# 03_DO.net
KiCad netlist of a schematic drawn in Altium Designer
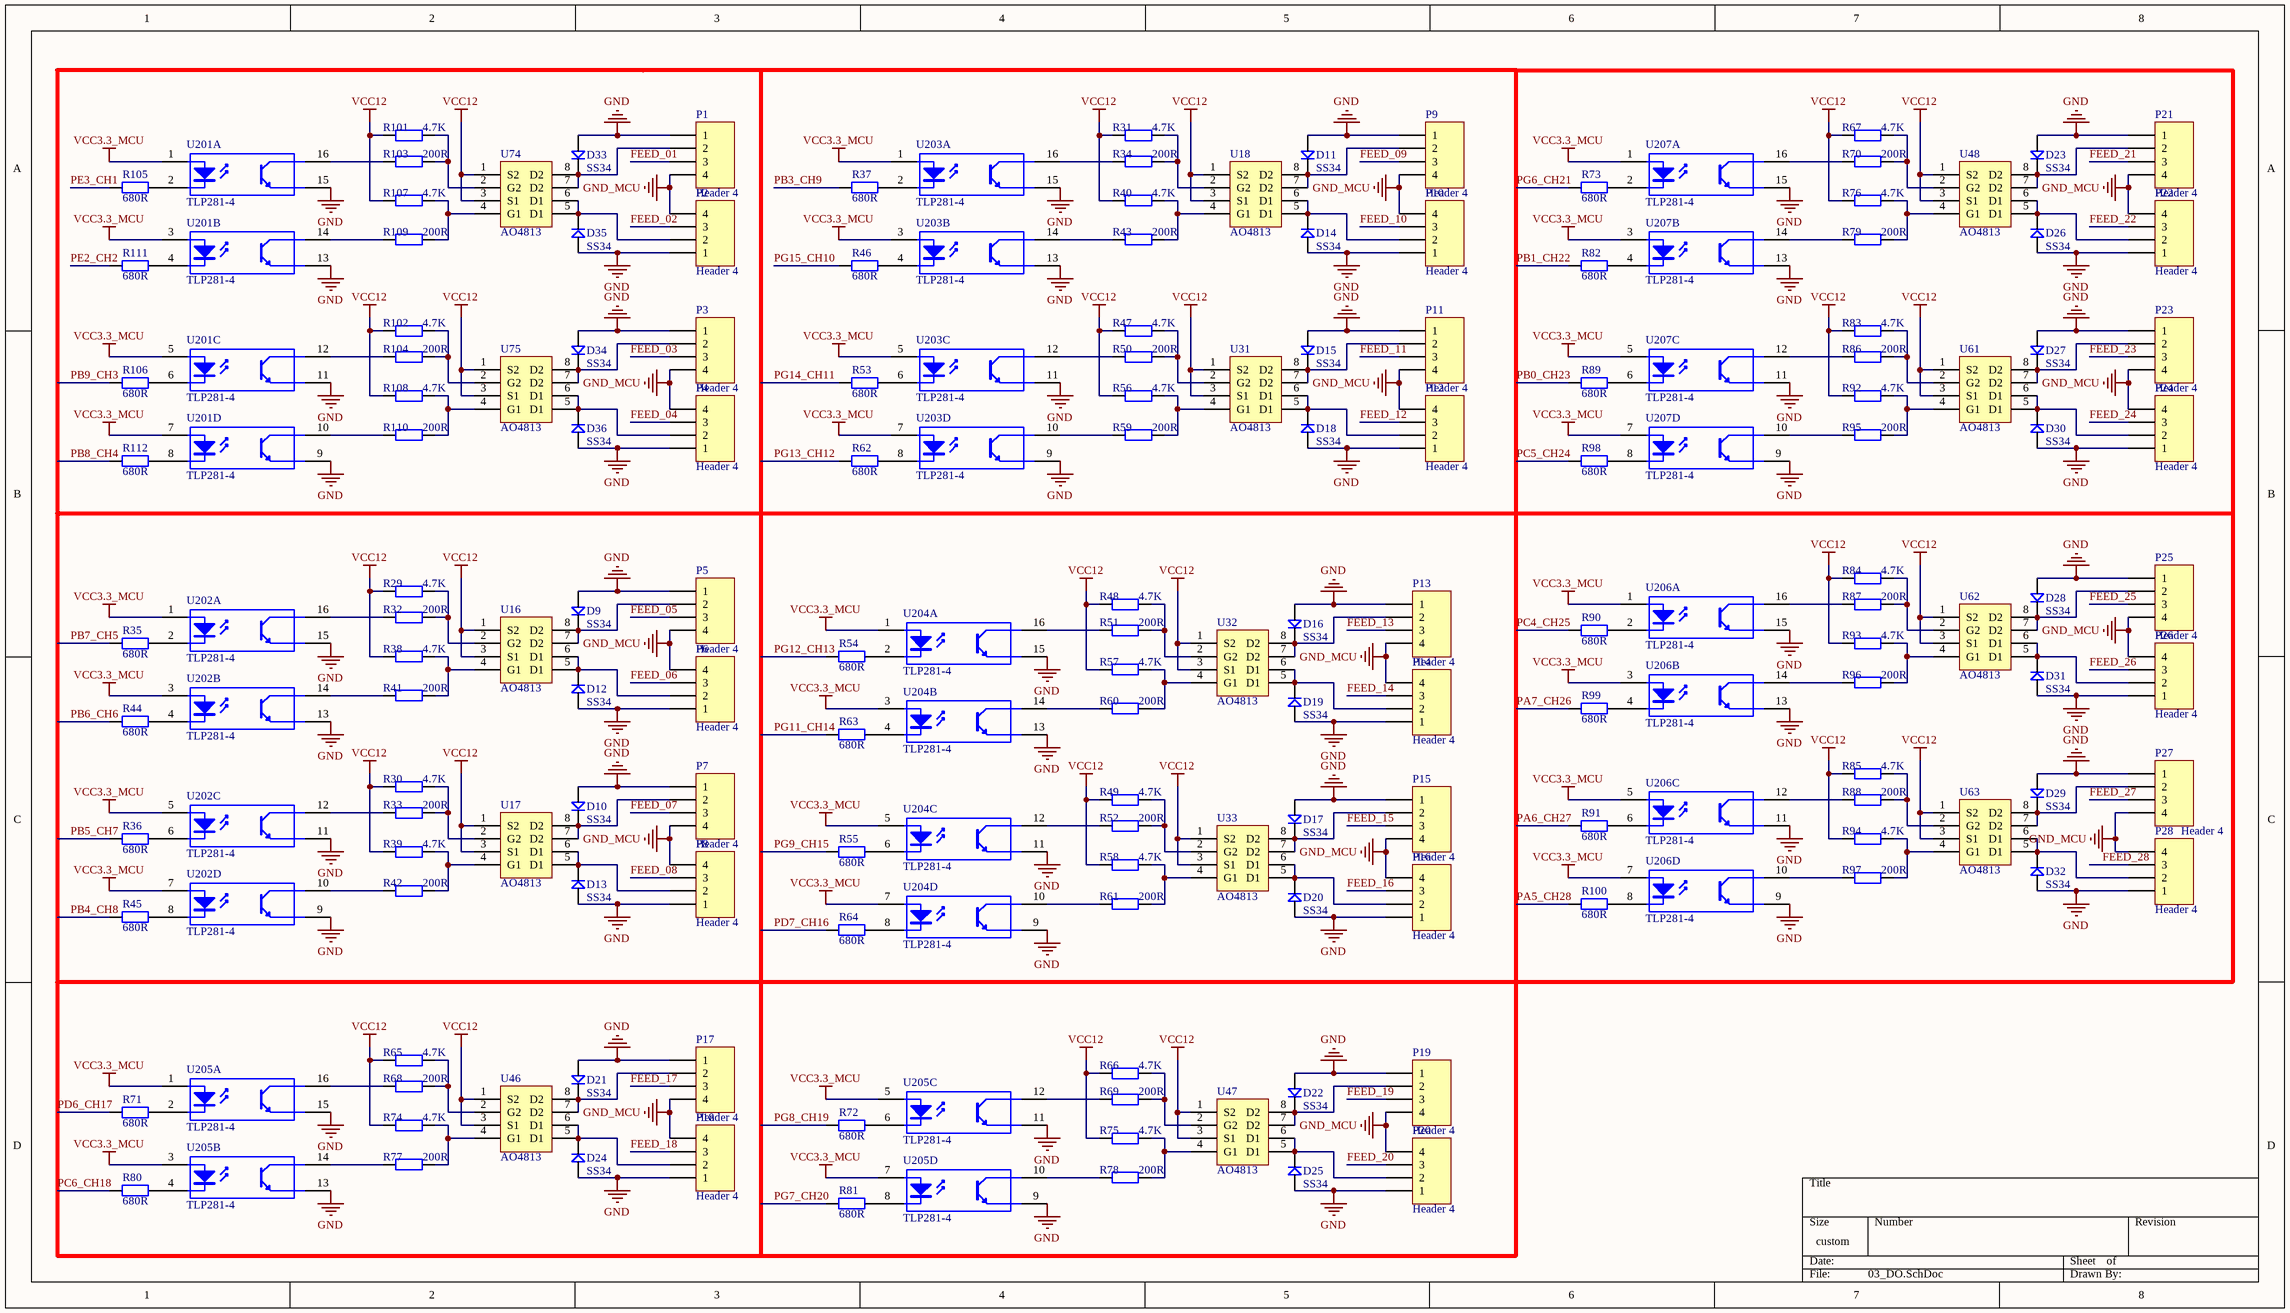
[diagram p0: 03_DO.SchDoc]

(export (version "E")
  (design (tool "Eeschema 10.0.6"))
  (components
    (comp (ref "D9") (value "SS34") (footprint "D1812") (libsource (lib "Explorer STM32F407封装库") (part "D")))
    (comp (ref "D10") (value "SS34") (footprint "D1812") (libsource (lib "Explorer STM32F407封装库") (part "D")))
    (comp (ref "D11") (value "SS34") (footprint "D1812") (libsource (lib "Explorer STM32F407封装库") (part "D")))
    (comp (ref "D12") (value "SS34") (footprint "D1812") (libsource (lib "Explorer STM32F407封装库") (part "D")))
    (comp (ref "D13") (value "SS34") (footprint "D1812") (libsource (lib "Explorer STM32F407封装库") (part "D")))
    (comp (ref "D14") (value "SS34") (footprint "D1812") (libsource (lib "Explorer STM32F407封装库") (part "D")))
    (comp (ref "D15") (value "SS34") (footprint "D1812") (libsource (lib "Explorer STM32F407封装库") (part "D")))
    (comp (ref "D16") (value "SS34") (footprint "D1812") (libsource (lib "Explorer STM32F407封装库") (part "D")))
    (comp (ref "D17") (value "SS34") (footprint "D1812") (libsource (lib "Explorer STM32F407封装库") (part "D")))
    (comp (ref "D18") (value "SS34") (footprint "D1812") (libsource (lib "Explorer STM32F407封装库") (part "D")))
    (comp (ref "D19") (value "SS34") (footprint "D1812") (libsource (lib "Explorer STM32F407封装库") (part "D")))
    (comp (ref "D20") (value "SS34") (footprint "D1812") (libsource (lib "Explorer STM32F407封装库") (part "D")))
    (comp (ref "D21") (value "SS34") (footprint "D1812") (libsource (lib "Explorer STM32F407封装库") (part "D")))
    (comp (ref "D22") (value "SS34") (footprint "D1812") (libsource (lib "Explorer STM32F407封装库") (part "D")))
    (comp (ref "D23") (value "SS34") (footprint "D1812") (libsource (lib "Explorer STM32F407封装库") (part "D")))
    (comp (ref "D24") (value "SS34") (footprint "D1812") (libsource (lib "Explorer STM32F407封装库") (part "D")))
    (comp (ref "D25") (value "SS34") (footprint "D1812") (libsource (lib "Explorer STM32F407封装库") (part "D")))
    (comp (ref "D26") (value "SS34") (footprint "D1812") (libsource (lib "Explorer STM32F407封装库") (part "D")))
    (comp (ref "D27") (value "SS34") (footprint "D1812") (libsource (lib "Explorer STM32F407封装库") (part "D")))
    (comp (ref "D28") (value "SS34") (footprint "D1812") (libsource (lib "Explorer STM32F407封装库") (part "D")))
    (comp (ref "D29") (value "SS34") (footprint "D1812") (libsource (lib "Explorer STM32F407封装库") (part "D")))
    (comp (ref "D30") (value "SS34") (footprint "D1812") (libsource (lib "Explorer STM32F407封装库") (part "D")))
    (comp (ref "D31") (value "SS34") (footprint "D1812") (libsource (lib "Explorer STM32F407封装库") (part "D")))
    (comp (ref "D32") (value "SS34") (footprint "D1812") (libsource (lib "Explorer STM32F407封装库") (part "D")))
    (comp (ref "D33") (value "SS34") (footprint "D1812") (libsource (lib "Explorer STM32F407封装库") (part "D")))
    (comp (ref "D34") (value "SS34") (footprint "D1812") (libsource (lib "Explorer STM32F407封装库") (part "D")))
    (comp (ref "D35") (value "SS34") (footprint "D1812") (libsource (lib "Explorer STM32F407封装库") (part "D")))
    (comp (ref "D36") (value "SS34") (footprint "D1812") (libsource (lib "Explorer STM32F407封装库") (part "D")))
    (comp (ref "P1")
      (value "Header 4")
      (footprint "XH2.54-1*10")
      (description "Header, 4-Pin")
      (fields (field (name "PUBLISHER") "Altium Limited"))
      (libsource (lib "Miscellaneous Connectors") (part "Header 4"))
    )
    (comp (ref "P2")
      (value "Header 4")
      (footprint "XH2.54-1*10")
      (description "Header, 4-Pin")
      (fields (field (name "PUBLISHER") "Altium Limited"))
      (libsource (lib "") (part "Header 4_1"))
    )
    (comp (ref "P3")
      (value "Header 4")
      (footprint "XH2.54-1*10")
      (description "Header, 4-Pin")
      (fields (field (name "PUBLISHER") "Altium Limited"))
      (libsource (lib "Miscellaneous Connectors") (part "Header 4"))
    )
    (comp (ref "P4")
      (value "Header 4")
      (footprint "XH2.54-1*10")
      (description "Header, 4-Pin")
      (fields (field (name "PUBLISHER") "Altium Limited"))
      (libsource (lib "") (part "Header 4_1"))
    )
    (comp (ref "P5")
      (value "Header 4")
      (footprint "XH2.54-1*10")
      (description "Header, 4-Pin")
      (fields (field (name "PUBLISHER") "Altium Limited"))
      (libsource (lib "Miscellaneous Connectors") (part "Header 4"))
    )
    (comp (ref "P6")
      (value "Header 4")
      (footprint "XH2.54-1*10")
      (description "Header, 4-Pin")
      (fields (field (name "PUBLISHER") "Altium Limited"))
      (libsource (lib "") (part "Header 4_1"))
    )
    (comp (ref "P7")
      (value "Header 4")
      (footprint "XH2.54-1*10")
      (description "Header, 4-Pin")
      (fields (field (name "PUBLISHER") "Altium Limited"))
      (libsource (lib "Miscellaneous Connectors") (part "Header 4"))
    )
    (comp (ref "P8")
      (value "Header 4")
      (footprint "XH2.54-1*10")
      (description "Header, 4-Pin")
      (fields (field (name "PUBLISHER") "Altium Limited"))
      (libsource (lib "") (part "Header 4_1"))
    )
    (comp (ref "P9")
      (value "Header 4")
      (footprint "XH2.54-1*10")
      (description "Header, 4-Pin")
      (fields (field (name "PUBLISHER") "Altium Limited"))
      (libsource (lib "Miscellaneous Connectors") (part "Header 4"))
    )
    (comp (ref "P10")
      (value "Header 4")
      (footprint "XH2.54-1*10")
      (description "Header, 4-Pin")
      (fields (field (name "PUBLISHER") "Altium Limited"))
      (libsource (lib "") (part "Header 4_1"))
    )
    (comp (ref "P11")
      (value "Header 4")
      (footprint "XH2.54-1*10")
      (description "Header, 4-Pin")
      (fields (field (name "PUBLISHER") "Altium Limited"))
      (libsource (lib "Miscellaneous Connectors") (part "Header 4"))
    )
    (comp (ref "P12")
      (value "Header 4")
      (footprint "XH2.54-1*10")
      (description "Header, 4-Pin")
      (fields (field (name "PUBLISHER") "Altium Limited"))
      (libsource (lib "") (part "Header 4_1"))
    )
    (comp (ref "P13")
      (value "Header 4")
      (footprint "XH2.54-1*10")
      (description "Header, 4-Pin")
      (fields (field (name "PUBLISHER") "Altium Limited"))
      (libsource (lib "Miscellaneous Connectors") (part "Header 4"))
    )
    (comp (ref "P14")
      (value "Header 4")
      (footprint "XH2.54-1*10")
      (description "Header, 4-Pin")
      (fields (field (name "PUBLISHER") "Altium Limited"))
      (libsource (lib "") (part "Header 4_1"))
    )
    (comp (ref "P15")
      (value "Header 4")
      (footprint "XH2.54-1*10")
      (description "Header, 4-Pin")
      (fields (field (name "PUBLISHER") "Altium Limited"))
      (libsource (lib "Miscellaneous Connectors") (part "Header 4"))
    )
    (comp (ref "P16")
      (value "Header 4")
      (footprint "XH2.54-1*10")
      (description "Header, 4-Pin")
      (fields (field (name "PUBLISHER") "Altium Limited"))
      (libsource (lib "") (part "Header 4_1"))
    )
    (comp (ref "P17")
      (value "Header 4")
      (footprint "XH2.54-1*10")
      (description "Header, 4-Pin")
      (fields (field (name "PUBLISHER") "Altium Limited"))
      (libsource (lib "Miscellaneous Connectors") (part "Header 4"))
    )
    (comp (ref "P18")
      (value "Header 4")
      (footprint "XH2.54-1*10")
      (description "Header, 4-Pin")
      (fields (field (name "PUBLISHER") "Altium Limited"))
      (libsource (lib "") (part "Header 4_1"))
    )
    (comp (ref "P19")
      (value "Header 4")
      (footprint "XH2.54-1*10")
      (description "Header, 4-Pin")
      (fields (field (name "PUBLISHER") "Altium Limited"))
      (libsource (lib "Miscellaneous Connectors") (part "Header 4"))
    )
    (comp (ref "P20")
      (value "Header 4")
      (footprint "XH2.54-1*10")
      (description "Header, 4-Pin")
      (fields (field (name "PUBLISHER") "Altium Limited"))
      (libsource (lib "") (part "Header 4_1"))
    )
    (comp (ref "P21")
      (value "Header 4")
      (footprint "XH2.54-1*10")
      (description "Header, 4-Pin")
      (fields (field (name "PUBLISHER") "Altium Limited"))
      (libsource (lib "Miscellaneous Connectors") (part "Header 4"))
    )
    (comp (ref "P22")
      (value "Header 4")
      (footprint "XH2.54-1*10")
      (description "Header, 4-Pin")
      (fields (field (name "PUBLISHER") "Altium Limited"))
      (libsource (lib "") (part "Header 4_1"))
    )
    (comp (ref "P23")
      (value "Header 4")
      (footprint "XH2.54-1*10")
      (description "Header, 4-Pin")
      (fields (field (name "PUBLISHER") "Altium Limited"))
      (libsource (lib "Miscellaneous Connectors") (part "Header 4"))
    )
    (comp (ref "P24")
      (value "Header 4")
      (footprint "XH2.54-1*10")
      (description "Header, 4-Pin")
      (fields (field (name "PUBLISHER") "Altium Limited"))
      (libsource (lib "") (part "Header 4_1"))
    )
    (comp (ref "P25")
      (value "Header 4")
      (footprint "XH2.54-1*10")
      (description "Header, 4-Pin")
      (fields (field (name "PUBLISHER") "Altium Limited"))
      (libsource (lib "Miscellaneous Connectors") (part "Header 4"))
    )
    (comp (ref "P26")
      (value "Header 4")
      (footprint "XH2.54-1*10")
      (description "Header, 4-Pin")
      (fields (field (name "PUBLISHER") "Altium Limited"))
      (libsource (lib "") (part "Header 4_1"))
    )
    (comp (ref "P27")
      (value "Header 4")
      (footprint "XH2.54-1*10")
      (description "Header, 4-Pin")
      (fields (field (name "PUBLISHER") "Altium Limited"))
      (libsource (lib "Miscellaneous Connectors") (part "Header 4"))
    )
    (comp (ref "P28")
      (value "Header 4")
      (footprint "XH2.54-1*10")
      (description "Header, 4-Pin")
      (fields (field (name "PUBLISHER") "Altium Limited"))
      (libsource (lib "") (part "Header 4_1"))
    )
    (comp (ref "R29")
      (value "4.7K")
      (footprint "0603R")
      (description "贴片电阻")
      (libsource (lib "Miscellaneous Devices LC") (part "0603 2.7KΩ (2701) 1%"))
    )
    (comp (ref "R30")
      (value "4.7K")
      (footprint "0603R")
      (description "贴片电阻")
      (libsource (lib "Miscellaneous Devices LC") (part "0603 2.7KΩ (2701) 1%"))
    )
    (comp (ref "R31")
      (value "4.7K")
      (footprint "0603R")
      (description "贴片电阻")
      (libsource (lib "Miscellaneous Devices LC") (part "0603 2.7KΩ (2701) 1%"))
    )
    (comp (ref "R32")
      (value "200R")
      (footprint "0603R")
      (description "贴片电阻")
      (libsource (lib "CD's_LIB_2018") (part "0603 2.7KΩ (2701) 1%"))
    )
    (comp (ref "R33")
      (value "200R")
      (footprint "0603R")
      (description "贴片电阻")
      (libsource (lib "CD's_LIB_2018") (part "0603 2.7KΩ (2701) 1%"))
    )
    (comp (ref "R34")
      (value "200R")
      (footprint "0603R")
      (description "贴片电阻")
      (libsource (lib "CD's_LIB_2018") (part "0603 2.7KΩ (2701) 1%"))
    )
    (comp (ref "R35")
      (value "680R")
      (footprint "0603R")
      (description "贴片电阻")
      (libsource (lib "CD's_LIB_2018") (part "0603 2.7KΩ (2701) 1%"))
    )
    (comp (ref "R36")
      (value "680R")
      (footprint "0603R")
      (description "贴片电阻")
      (libsource (lib "CD's_LIB_2018") (part "0603 2.7KΩ (2701) 1%"))
    )
    (comp (ref "R37")
      (value "680R")
      (footprint "0603R")
      (description "贴片电阻")
      (libsource (lib "CD's_LIB_2018") (part "0603 2.7KΩ (2701) 1%"))
    )
    (comp (ref "R38")
      (value "4.7K")
      (footprint "0603R")
      (description "贴片电阻")
      (libsource (lib "Miscellaneous Devices LC") (part "0603 2.7KΩ (2701) 1%"))
    )
    (comp (ref "R39")
      (value "4.7K")
      (footprint "0603R")
      (description "贴片电阻")
      (libsource (lib "Miscellaneous Devices LC") (part "0603 2.7KΩ (2701) 1%"))
    )
    (comp (ref "R40")
      (value "4.7K")
      (footprint "0603R")
      (description "贴片电阻")
      (libsource (lib "Miscellaneous Devices LC") (part "0603 2.7KΩ (2701) 1%"))
    )
    (comp (ref "R41")
      (value "200R")
      (footprint "0603R")
      (description "贴片电阻")
      (libsource (lib "CD's_LIB_2018") (part "0603 2.7KΩ (2701) 1%"))
    )
    (comp (ref "R42")
      (value "200R")
      (footprint "0603R")
      (description "贴片电阻")
      (libsource (lib "CD's_LIB_2018") (part "0603 2.7KΩ (2701) 1%"))
    )
    (comp (ref "R43")
      (value "200R")
      (footprint "0603R")
      (description "贴片电阻")
      (libsource (lib "CD's_LIB_2018") (part "0603 2.7KΩ (2701) 1%"))
    )
    (comp (ref "R44")
      (value "680R")
      (footprint "0603R")
      (description "贴片电阻")
      (libsource (lib "CD's_LIB_2018") (part "0603 2.7KΩ (2701) 1%"))
    )
    (comp (ref "R45")
      (value "680R")
      (footprint "0603R")
      (description "贴片电阻")
      (libsource (lib "CD's_LIB_2018") (part "0603 2.7KΩ (2701) 1%"))
    )
    (comp (ref "R46")
      (value "680R")
      (footprint "0603R")
      (description "贴片电阻")
      (libsource (lib "CD's_LIB_2018") (part "0603 2.7KΩ (2701) 1%"))
    )
    (comp (ref "R47")
      (value "4.7K")
      (footprint "0603R")
      (description "贴片电阻")
      (libsource (lib "Miscellaneous Devices LC") (part "0603 2.7KΩ (2701) 1%"))
    )
    (comp (ref "R48")
      (value "4.7K")
      (footprint "0603R")
      (description "贴片电阻")
      (libsource (lib "Miscellaneous Devices LC") (part "0603 2.7KΩ (2701) 1%"))
    )
    (comp (ref "R49")
      (value "4.7K")
      (footprint "0603R")
      (description "贴片电阻")
      (libsource (lib "Miscellaneous Devices LC") (part "0603 2.7KΩ (2701) 1%"))
    )
    (comp (ref "R50")
      (value "200R")
      (footprint "0603R")
      (description "贴片电阻")
      (libsource (lib "CD's_LIB_2018") (part "0603 2.7KΩ (2701) 1%"))
    )
    (comp (ref "R51")
      (value "200R")
      (footprint "0603R")
      (description "贴片电阻")
      (libsource (lib "CD's_LIB_2018") (part "0603 2.7KΩ (2701) 1%"))
    )
    (comp (ref "R52")
      (value "200R")
      (footprint "0603R")
      (description "贴片电阻")
      (libsource (lib "CD's_LIB_2018") (part "0603 2.7KΩ (2701) 1%"))
    )
    (comp (ref "R53")
      (value "680R")
      (footprint "0603R")
      (description "贴片电阻")
      (libsource (lib "CD's_LIB_2018") (part "0603 2.7KΩ (2701) 1%"))
    )
    (comp (ref "R54")
      (value "680R")
      (footprint "0603R")
      (description "贴片电阻")
      (libsource (lib "CD's_LIB_2018") (part "0603 2.7KΩ (2701) 1%"))
    )
    (comp (ref "R55")
      (value "680R")
      (footprint "0603R")
      (description "贴片电阻")
      (libsource (lib "CD's_LIB_2018") (part "0603 2.7KΩ (2701) 1%"))
    )
    (comp (ref "R56")
      (value "4.7K")
      (footprint "0603R")
      (description "贴片电阻")
      (libsource (lib "Miscellaneous Devices LC") (part "0603 2.7KΩ (2701) 1%"))
    )
    (comp (ref "R57")
      (value "4.7K")
      (footprint "0603R")
      (description "贴片电阻")
      (libsource (lib "Miscellaneous Devices LC") (part "0603 2.7KΩ (2701) 1%"))
    )
    (comp (ref "R58")
      (value "4.7K")
      (footprint "0603R")
      (description "贴片电阻")
      (libsource (lib "Miscellaneous Devices LC") (part "0603 2.7KΩ (2701) 1%"))
    )
    (comp (ref "R59")
      (value "200R")
      (footprint "0603R")
      (description "贴片电阻")
      (libsource (lib "CD's_LIB_2018") (part "0603 2.7KΩ (2701) 1%"))
    )
    (comp (ref "R60")
      (value "200R")
      (footprint "0603R")
      (description "贴片电阻")
      (libsource (lib "CD's_LIB_2018") (part "0603 2.7KΩ (2701) 1%"))
    )
    (comp (ref "R61")
      (value "200R")
      (footprint "0603R")
      (description "贴片电阻")
      (libsource (lib "CD's_LIB_2018") (part "0603 2.7KΩ (2701) 1%"))
    )
    (comp (ref "R62")
      (value "680R")
      (footprint "0603R")
      (description "贴片电阻")
      (libsource (lib "CD's_LIB_2018") (part "0603 2.7KΩ (2701) 1%"))
    )
    (comp (ref "R63")
      (value "680R")
      (footprint "0603R")
      (description "贴片电阻")
      (libsource (lib "CD's_LIB_2018") (part "0603 2.7KΩ (2701) 1%"))
    )
    (comp (ref "R64")
      (value "680R")
      (footprint "0603R")
      (description "贴片电阻")
      (libsource (lib "CD's_LIB_2018") (part "0603 2.7KΩ (2701) 1%"))
    )
    (comp (ref "R65")
      (value "4.7K")
      (footprint "0603R")
      (description "贴片电阻")
      (libsource (lib "Miscellaneous Devices LC") (part "0603 2.7KΩ (2701) 1%"))
    )
    (comp (ref "R66")
      (value "4.7K")
      (footprint "0603R")
      (description "贴片电阻")
      (libsource (lib "Miscellaneous Devices LC") (part "0603 2.7KΩ (2701) 1%"))
    )
    (comp (ref "R67")
      (value "4.7K")
      (footprint "0603R")
      (description "贴片电阻")
      (libsource (lib "Miscellaneous Devices LC") (part "0603 2.7KΩ (2701) 1%"))
    )
    (comp (ref "R68")
      (value "200R")
      (footprint "0603R")
      (description "贴片电阻")
      (libsource (lib "CD's_LIB_2018") (part "0603 2.7KΩ (2701) 1%"))
    )
    (comp (ref "R69")
      (value "200R")
      (footprint "0603R")
      (description "贴片电阻")
      (libsource (lib "CD's_LIB_2018") (part "0603 2.7KΩ (2701) 1%"))
    )
    (comp (ref "R70")
      (value "200R")
      (footprint "0603R")
      (description "贴片电阻")
      (libsource (lib "CD's_LIB_2018") (part "0603 2.7KΩ (2701) 1%"))
    )
    (comp (ref "R71")
      (value "680R")
      (footprint "0603R")
      (description "贴片电阻")
      (libsource (lib "CD's_LIB_2018") (part "0603 2.7KΩ (2701) 1%"))
    )
    (comp (ref "R72")
      (value "680R")
      (footprint "0603R")
      (description "贴片电阻")
      (libsource (lib "CD's_LIB_2018") (part "0603 2.7KΩ (2701) 1%"))
    )
    (comp (ref "R73")
      (value "680R")
      (footprint "0603R")
      (description "贴片电阻")
      (libsource (lib "CD's_LIB_2018") (part "0603 2.7KΩ (2701) 1%"))
    )
    (comp (ref "R74")
      (value "4.7K")
      (footprint "0603R")
      (description "贴片电阻")
      (libsource (lib "Miscellaneous Devices LC") (part "0603 2.7KΩ (2701) 1%"))
    )
    (comp (ref "R75")
      (value "4.7K")
      (footprint "0603R")
      (description "贴片电阻")
      (libsource (lib "Miscellaneous Devices LC") (part "0603 2.7KΩ (2701) 1%"))
    )
    (comp (ref "R76")
      (value "4.7K")
      (footprint "0603R")
      (description "贴片电阻")
      (libsource (lib "Miscellaneous Devices LC") (part "0603 2.7KΩ (2701) 1%"))
    )
    (comp (ref "R77")
      (value "200R")
      (footprint "0603R")
      (description "贴片电阻")
      (libsource (lib "CD's_LIB_2018") (part "0603 2.7KΩ (2701) 1%"))
    )
    (comp (ref "R78")
      (value "200R")
      (footprint "0603R")
      (description "贴片电阻")
      (libsource (lib "CD's_LIB_2018") (part "0603 2.7KΩ (2701) 1%"))
    )
    (comp (ref "R79")
      (value "200R")
      (footprint "0603R")
      (description "贴片电阻")
      (libsource (lib "CD's_LIB_2018") (part "0603 2.7KΩ (2701) 1%"))
    )
    (comp (ref "R80")
      (value "680R")
      (footprint "0603R")
      (description "贴片电阻")
      (libsource (lib "CD's_LIB_2018") (part "0603 2.7KΩ (2701) 1%"))
    )
    (comp (ref "R81")
      (value "680R")
      (footprint "0603R")
      (description "贴片电阻")
      (libsource (lib "CD's_LIB_2018") (part "0603 2.7KΩ (2701) 1%"))
    )
    (comp (ref "R82")
      (value "680R")
      (footprint "0603R")
      (description "贴片电阻")
      (libsource (lib "CD's_LIB_2018") (part "0603 2.7KΩ (2701) 1%"))
    )
    (comp (ref "R83")
      (value "4.7K")
      (footprint "0603R")
      (description "贴片电阻")
      (libsource (lib "Miscellaneous Devices LC") (part "0603 2.7KΩ (2701) 1%"))
    )
    (comp (ref "R84")
      (value "4.7K")
      (footprint "0603R")
      (description "贴片电阻")
      (libsource (lib "Miscellaneous Devices LC") (part "0603 2.7KΩ (2701) 1%"))
    )
    (comp (ref "R85")
      (value "4.7K")
      (footprint "0603R")
      (description "贴片电阻")
      (libsource (lib "Miscellaneous Devices LC") (part "0603 2.7KΩ (2701) 1%"))
    )
    (comp (ref "R86")
      (value "200R")
      (footprint "0603R")
      (description "贴片电阻")
      (libsource (lib "CD's_LIB_2018") (part "0603 2.7KΩ (2701) 1%"))
    )
    (comp (ref "R87")
      (value "200R")
      (footprint "0603R")
      (description "贴片电阻")
      (libsource (lib "CD's_LIB_2018") (part "0603 2.7KΩ (2701) 1%"))
    )
    (comp (ref "R88")
      (value "200R")
      (footprint "0603R")
      (description "贴片电阻")
      (libsource (lib "CD's_LIB_2018") (part "0603 2.7KΩ (2701) 1%"))
    )
    (comp (ref "R89")
      (value "680R")
      (footprint "0603R")
      (description "贴片电阻")
      (libsource (lib "CD's_LIB_2018") (part "0603 2.7KΩ (2701) 1%"))
    )
    (comp (ref "R90")
      (value "680R")
      (footprint "0603R")
      (description "贴片电阻")
      (libsource (lib "CD's_LIB_2018") (part "0603 2.7KΩ (2701) 1%"))
    )
    (comp (ref "R91")
      (value "680R")
      (footprint "0603R")
      (description "贴片电阻")
      (libsource (lib "CD's_LIB_2018") (part "0603 2.7KΩ (2701) 1%"))
    )
    (comp (ref "R92")
      (value "4.7K")
      (footprint "0603R")
      (description "贴片电阻")
      (libsource (lib "Miscellaneous Devices LC") (part "0603 2.7KΩ (2701) 1%"))
    )
    (comp (ref "R93")
      (value "4.7K")
      (footprint "0603R")
      (description "贴片电阻")
      (libsource (lib "Miscellaneous Devices LC") (part "0603 2.7KΩ (2701) 1%"))
    )
    (comp (ref "R94")
      (value "4.7K")
      (footprint "0603R")
      (description "贴片电阻")
      (libsource (lib "Miscellaneous Devices LC") (part "0603 2.7KΩ (2701) 1%"))
    )
    (comp (ref "R95")
      (value "200R")
      (footprint "0603R")
      (description "贴片电阻")
      (libsource (lib "CD's_LIB_2018") (part "0603 2.7KΩ (2701) 1%"))
    )
    (comp (ref "R96")
      (value "200R")
      (footprint "0603R")
      (description "贴片电阻")
      (libsource (lib "CD's_LIB_2018") (part "0603 2.7KΩ (2701) 1%"))
    )
    (comp (ref "R97")
      (value "200R")
      (footprint "0603R")
      (description "贴片电阻")
      (libsource (lib "CD's_LIB_2018") (part "0603 2.7KΩ (2701) 1%"))
    )
    (comp (ref "R98")
      (value "680R")
      (footprint "0603R")
      (description "贴片电阻")
      (libsource (lib "CD's_LIB_2018") (part "0603 2.7KΩ (2701) 1%"))
    )
    (comp (ref "R99")
      (value "680R")
      (footprint "0603R")
      (description "贴片电阻")
      (libsource (lib "CD's_LIB_2018") (part "0603 2.7KΩ (2701) 1%"))
    )
    (comp (ref "R100")
      (value "680R")
      (footprint "0603R")
      (description "贴片电阻")
      (libsource (lib "CD's_LIB_2018") (part "0603 2.7KΩ (2701) 1%"))
    )
    (comp (ref "R101")
      (value "4.7K")
      (footprint "0603R")
      (description "贴片电阻")
      (libsource (lib "Miscellaneous Devices LC") (part "0603 2.7KΩ (2701) 1%"))
    )
    (comp (ref "R102")
      (value "4.7K")
      (footprint "0603R")
      (description "贴片电阻")
      (libsource (lib "Miscellaneous Devices LC") (part "0603 2.7KΩ (2701) 1%"))
    )
    (comp (ref "R103")
      (value "200R")
      (footprint "0603R")
      (description "贴片电阻")
      (libsource (lib "CD's_LIB_2018") (part "0603 2.7KΩ (2701) 1%"))
    )
    (comp (ref "R104")
      (value "200R")
      (footprint "0603R")
      (description "贴片电阻")
      (libsource (lib "CD's_LIB_2018") (part "0603 2.7KΩ (2701) 1%"))
    )
    (comp (ref "R105")
      (value "680R")
      (footprint "0603R")
      (description "贴片电阻")
      (libsource (lib "CD's_LIB_2018") (part "0603 2.7KΩ (2701) 1%"))
    )
    (comp (ref "R106")
      (value "680R")
      (footprint "0603R")
      (description "贴片电阻")
      (libsource (lib "CD's_LIB_2018") (part "0603 2.7KΩ (2701) 1%"))
    )
    (comp (ref "R107")
      (value "4.7K")
      (footprint "0603R")
      (description "贴片电阻")
      (libsource (lib "Miscellaneous Devices LC") (part "0603 2.7KΩ (2701) 1%"))
    )
    (comp (ref "R108")
      (value "4.7K")
      (footprint "0603R")
      (description "贴片电阻")
      (libsource (lib "Miscellaneous Devices LC") (part "0603 2.7KΩ (2701) 1%"))
    )
    (comp (ref "R109")
      (value "200R")
      (footprint "0603R")
      (description "贴片电阻")
      (libsource (lib "CD's_LIB_2018") (part "0603 2.7KΩ (2701) 1%"))
    )
    (comp (ref "R110")
      (value "200R")
      (footprint "0603R")
      (description "贴片电阻")
      (libsource (lib "CD's_LIB_2018") (part "0603 2.7KΩ (2701) 1%"))
    )
    (comp (ref "R111")
      (value "680R")
      (footprint "0603R")
      (description "贴片电阻")
      (libsource (lib "CD's_LIB_2018") (part "0603 2.7KΩ (2701) 1%"))
    )
    (comp (ref "R112")
      (value "680R")
      (footprint "0603R")
      (description "贴片电阻")
      (libsource (lib "CD's_LIB_2018") (part "0603 2.7KΩ (2701) 1%"))
    )
    (comp (ref "U16") (value "AO4813") (footprint "SO-8") (libsource (lib "NDS8434") (part "NDS8434")))
    (comp (ref "U17") (value "AO4813") (footprint "SO-8") (libsource (lib "NDS8434") (part "NDS8434")))
    (comp (ref "U18") (value "AO4813") (footprint "SO-8") (libsource (lib "NDS8434") (part "NDS8434")))
    (comp (ref "U31") (value "AO4813") (footprint "SO-8") (libsource (lib "NDS8434") (part "NDS8434")))
    (comp (ref "U32") (value "AO4813") (footprint "SO-8") (libsource (lib "NDS8434") (part "NDS8434")))
    (comp (ref "U33") (value "AO4813") (footprint "SO-8") (libsource (lib "NDS8434") (part "NDS8434")))
    (comp (ref "U46") (value "AO4813") (footprint "SO-8") (libsource (lib "NDS8434") (part "NDS8434")))
    (comp (ref "U47") (value "AO4813") (footprint "SO-8") (libsource (lib "NDS8434") (part "NDS8434")))
    (comp (ref "U48") (value "AO4813") (footprint "SO-8") (libsource (lib "NDS8434") (part "NDS8434")))
    (comp (ref "U61") (value "AO4813") (footprint "SO-8") (libsource (lib "NDS8434") (part "NDS8434")))
    (comp (ref "U62") (value "AO4813") (footprint "SO-8") (libsource (lib "NDS8434") (part "NDS8434")))
    (comp (ref "U63") (value "AO4813") (footprint "SO-8") (libsource (lib "NDS8434") (part "NDS8434")))
    (comp (ref "U74") (value "AO4813") (footprint "SO-8") (libsource (lib "NDS8434") (part "NDS8434")))
    (comp (ref "U75") (value "AO4813") (footprint "SO-8") (libsource (lib "NDS8434") (part "NDS8434")))
    (comp (ref "U201")
      (value "TLP281-4")
      (footprint "SO-16")
      (libsource (lib "CD's_LIB_2018") (part "TP521-4_1"))
    )
    (comp (ref "U202")
      (value "TLP281-4")
      (footprint "SO-16")
      (libsource (lib "CD's_LIB_2018") (part "TP521-4_1"))
    )
    (comp (ref "U203")
      (value "TLP281-4")
      (footprint "SO-16")
      (libsource (lib "CD's_LIB_2018") (part "TP521-4_1"))
    )
    (comp (ref "U204")
      (value "TLP281-4")
      (footprint "SO-16")
      (libsource (lib "CD's_LIB_2018") (part "TP521-4_1"))
    )
    (comp (ref "U205")
      (value "TLP281-4")
      (footprint "SO-16")
      (libsource (lib "CD's_LIB_2018") (part "TP521-4_1"))
    )
    (comp (ref "U206")
      (value "TLP281-4")
      (footprint "SO-16")
      (libsource (lib "CD's_LIB_2018") (part "TP521-4_1"))
    )
    (comp (ref "U207")
      (value "TLP281-4")
      (footprint "SO-16")
      (libsource (lib "CD's_LIB_2018") (part "TP521-4_1"))
    )
  )
  (nets
    (net (code "1") (name "/FEED_01") (class "Default")
      (node (ref "P1") (pin "3") (pinfunction "3_3") (pintype "passive"))
    )
    (net (code "2") (name "/FEED_02") (class "Default")
      (node (ref "P2") (pin "3") (pinfunction "3_3") (pintype "passive"))
    )
    (net (code "3") (name "/FEED_03") (class "Default")
      (node (ref "P3") (pin "3") (pinfunction "3_3") (pintype "passive"))
    )
    (net (code "4") (name "/FEED_04") (class "Default")
      (node (ref "P4") (pin "3") (pinfunction "3_3") (pintype "passive"))
    )
    (net (code "5") (name "/FEED_05") (class "Default")
      (node (ref "P5") (pin "3") (pinfunction "3_3") (pintype "passive"))
    )
    (net (code "6") (name "/FEED_06") (class "Default")
      (node (ref "P6") (pin "3") (pinfunction "3_3") (pintype "passive"))
    )
    (net (code "7") (name "/FEED_07") (class "Default")
      (node (ref "P7") (pin "3") (pinfunction "3_3") (pintype "passive"))
    )
    (net (code "8") (name "/FEED_08") (class "Default")
      (node (ref "P8") (pin "3") (pinfunction "3_3") (pintype "passive"))
    )
    (net (code "9") (name "/FEED_09") (class "Default")
      (node (ref "P9") (pin "3") (pinfunction "3_3") (pintype "passive"))
    )
    (net (code "10") (name "/FEED_10") (class "Default")
      (node (ref "P10") (pin "3") (pinfunction "3_3") (pintype "passive"))
    )
    (net (code "11") (name "/FEED_11") (class "Default")
      (node (ref "P11") (pin "3") (pinfunction "3_3") (pintype "passive"))
    )
    (net (code "12") (name "/FEED_12") (class "Default")
      (node (ref "P12") (pin "3") (pinfunction "3_3") (pintype "passive"))
    )
    (net (code "13") (name "/FEED_13") (class "Default")
      (node (ref "P13") (pin "3") (pinfunction "3_3") (pintype "passive"))
    )
    (net (code "14") (name "/FEED_14") (class "Default")
      (node (ref "P14") (pin "3") (pinfunction "3_3") (pintype "passive"))
    )
    (net (code "15") (name "/FEED_15") (class "Default")
      (node (ref "P15") (pin "3") (pinfunction "3_3") (pintype "passive"))
    )
    (net (code "16") (name "/FEED_16") (class "Default")
      (node (ref "P16") (pin "3") (pinfunction "3_3") (pintype "passive"))
    )
    (net (code "17") (name "/FEED_17") (class "Default")
      (node (ref "P17") (pin "3") (pinfunction "3_3") (pintype "passive"))
    )
    (net (code "18") (name "/FEED_18") (class "Default")
      (node (ref "P18") (pin "3") (pinfunction "3_3") (pintype "passive"))
    )
    (net (code "19") (name "/FEED_19") (class "Default")
      (node (ref "P19") (pin "3") (pinfunction "3_3") (pintype "passive"))
    )
    (net (code "20") (name "/FEED_20") (class "Default")
      (node (ref "P20") (pin "3") (pinfunction "3_3") (pintype "passive"))
    )
    (net (code "21") (name "/FEED_21") (class "Default")
      (node (ref "P21") (pin "3") (pinfunction "3_3") (pintype "passive"))
    )
    (net (code "22") (name "/FEED_22") (class "Default")
      (node (ref "P22") (pin "3") (pinfunction "3_3") (pintype "passive"))
    )
    (net (code "23") (name "/FEED_23") (class "Default")
      (node (ref "P23") (pin "3") (pinfunction "3_3") (pintype "passive"))
    )
    (net (code "24") (name "/FEED_24") (class "Default")
      (node (ref "P24") (pin "3") (pinfunction "3_3") (pintype "passive"))
    )
    (net (code "25") (name "/FEED_25") (class "Default")
      (node (ref "P25") (pin "3") (pinfunction "3_3") (pintype "passive"))
    )
    (net (code "26") (name "/FEED_26") (class "Default")
      (node (ref "P26") (pin "3") (pinfunction "3_3") (pintype "passive"))
    )
    (net (code "27") (name "/FEED_27") (class "Default")
      (node (ref "P27") (pin "3") (pinfunction "3_3") (pintype "passive"))
    )
    (net (code "28") (name "/FEED_28") (class "Default")
      (node (ref "P28") (pin "3") (pinfunction "3_3") (pintype "passive"))
    )
    (net (code "29") (name "/PA5_CH28") (class "Default")
      (node (ref "R100") (pin "1") (pinfunction "1_1") (pintype "passive"))
    )
    (net (code "30") (name "/PA6_CH27") (class "Default")
      (node (ref "R91") (pin "1") (pinfunction "1_1") (pintype "passive"))
    )
    (net (code "31") (name "/PA7_CH26") (class "Default")
      (node (ref "R99") (pin "1") (pinfunction "1_1") (pintype "passive"))
    )
    (net (code "32") (name "/PB0_CH23") (class "Default")
      (node (ref "R89") (pin "1") (pinfunction "1_1") (pintype "passive"))
    )
    (net (code "33") (name "/PB1_CH22") (class "Default")
      (node (ref "R82") (pin "1") (pinfunction "1_1") (pintype "passive"))
    )
    (net (code "34") (name "/PB3_CH9") (class "Default")
      (node (ref "R37") (pin "1") (pinfunction "1_1") (pintype "passive"))
    )
    (net (code "35") (name "/PB4_CH8") (class "Default")
      (node (ref "R45") (pin "1") (pinfunction "1_1") (pintype "passive"))
    )
    (net (code "36") (name "/PB5_CH7") (class "Default")
      (node (ref "R36") (pin "1") (pinfunction "1_1") (pintype "passive"))
    )
    (net (code "37") (name "/PB6_CH6") (class "Default")
      (node (ref "R44") (pin "1") (pinfunction "1_1") (pintype "passive"))
    )
    (net (code "38") (name "/PB7_CH5") (class "Default")
      (node (ref "R35") (pin "1") (pinfunction "1_1") (pintype "passive"))
    )
    (net (code "39") (name "/PB8_CH4") (class "Default")
      (node (ref "R112") (pin "1") (pinfunction "1_1") (pintype "passive"))
    )
    (net (code "40") (name "/PB9_CH3") (class "Default")
      (node (ref "R106") (pin "1") (pinfunction "1_1") (pintype "passive"))
    )
    (net (code "41") (name "/PC4_CH25") (class "Default")
      (node (ref "R90") (pin "1") (pinfunction "1_1") (pintype "passive"))
    )
    (net (code "42") (name "/PC5_CH24") (class "Default")
      (node (ref "R98") (pin "1") (pinfunction "1_1") (pintype "passive"))
    )
    (net (code "43") (name "/PC6_CH18") (class "Default")
      (node (ref "R80") (pin "1") (pinfunction "1_1") (pintype "passive"))
    )
    (net (code "44") (name "/PD6_CH17") (class "Default")
      (node (ref "R71") (pin "1") (pinfunction "1_1") (pintype "passive"))
    )
    (net (code "45") (name "/PD7_CH16") (class "Default")
      (node (ref "R64") (pin "1") (pinfunction "1_1") (pintype "passive"))
    )
    (net (code "46") (name "/PE2_CH2") (class "Default")
      (node (ref "R111") (pin "1") (pinfunction "1_1") (pintype "passive"))
    )
    (net (code "47") (name "/PE3_CH1") (class "Default")
      (node (ref "R105") (pin "1") (pinfunction "1_1") (pintype "passive"))
    )
    (net (code "48") (name "/PG6_CH21") (class "Default")
      (node (ref "R73") (pin "1") (pinfunction "1_1") (pintype "passive"))
    )
    (net (code "49") (name "/PG7_CH20") (class "Default")
      (node (ref "R81") (pin "1") (pinfunction "1_1") (pintype "passive"))
    )
    (net (code "50") (name "/PG8_CH19") (class "Default")
      (node (ref "R72") (pin "1") (pinfunction "1_1") (pintype "passive"))
    )
    (net (code "51") (name "/PG9_CH15") (class "Default")
      (node (ref "R55") (pin "1") (pinfunction "1_1") (pintype "passive"))
    )
    (net (code "52") (name "/PG11_CH14") (class "Default")
      (node (ref "R63") (pin "1") (pinfunction "1_1") (pintype "passive"))
    )
    (net (code "53") (name "/PG12_CH13") (class "Default")
      (node (ref "R54") (pin "1") (pinfunction "1_1") (pintype "passive"))
    )
    (net (code "54") (name "/PG13_CH12") (class "Default")
      (node (ref "R62") (pin "1") (pinfunction "1_1") (pintype "passive"))
    )
    (net (code "55") (name "/PG14_CH11") (class "Default")
      (node (ref "R53") (pin "1") (pinfunction "1_1") (pintype "passive"))
    )
    (net (code "56") (name "/PG15_CH10") (class "Default")
      (node (ref "R46") (pin "1") (pinfunction "1_1") (pintype "passive"))
    )
    (net (code "57") (name "GND") (class "Default")
      (node (ref "D10") (pin "1") (pintype "passive"))
      (node (ref "D11") (pin "1") (pintype "passive"))
      (node (ref "D12") (pin "1") (pintype "passive"))
      (node (ref "D13") (pin "1") (pintype "passive"))
      (node (ref "D14") (pin "1") (pintype "passive"))
      (node (ref "D15") (pin "1") (pintype "passive"))
      (node (ref "D16") (pin "1") (pintype "passive"))
      (node (ref "D17") (pin "1") (pintype "passive"))
      (node (ref "D18") (pin "1") (pintype "passive"))
      (node (ref "D19") (pin "1") (pintype "passive"))
      (node (ref "D20") (pin "1") (pintype "passive"))
      (node (ref "D21") (pin "1") (pintype "passive"))
      (node (ref "D22") (pin "1") (pintype "passive"))
      (node (ref "D23") (pin "1") (pintype "passive"))
      (node (ref "D24") (pin "1") (pintype "passive"))
      (node (ref "D25") (pin "1") (pintype "passive"))
      (node (ref "D26") (pin "1") (pintype "passive"))
      (node (ref "D27") (pin "1") (pintype "passive"))
      (node (ref "D28") (pin "1") (pintype "passive"))
      (node (ref "D29") (pin "1") (pintype "passive"))
      (node (ref "D30") (pin "1") (pintype "passive"))
      (node (ref "D31") (pin "1") (pintype "passive"))
      (node (ref "D32") (pin "1") (pintype "passive"))
      (node (ref "D33") (pin "1") (pintype "passive"))
      (node (ref "D34") (pin "1") (pintype "passive"))
      (node (ref "D35") (pin "1") (pintype "passive"))
      (node (ref "D36") (pin "1") (pintype "passive"))
      (node (ref "D9") (pin "1") (pintype "passive"))
      (node (ref "P1") (pin "1") (pinfunction "1_1") (pintype "passive"))
      (node (ref "P10") (pin "1") (pinfunction "1_1") (pintype "passive"))
      (node (ref "P11") (pin "1") (pinfunction "1_1") (pintype "passive"))
      (node (ref "P12") (pin "1") (pinfunction "1_1") (pintype "passive"))
      (node (ref "P13") (pin "1") (pinfunction "1_1") (pintype "passive"))
      (node (ref "P14") (pin "1") (pinfunction "1_1") (pintype "passive"))
      (node (ref "P15") (pin "1") (pinfunction "1_1") (pintype "passive"))
      (node (ref "P16") (pin "1") (pinfunction "1_1") (pintype "passive"))
      (node (ref "P17") (pin "1") (pinfunction "1_1") (pintype "passive"))
      (node (ref "P18") (pin "1") (pinfunction "1_1") (pintype "passive"))
      (node (ref "P19") (pin "1") (pinfunction "1_1") (pintype "passive"))
      (node (ref "P2") (pin "1") (pinfunction "1_1") (pintype "passive"))
      (node (ref "P20") (pin "1") (pinfunction "1_1") (pintype "passive"))
      (node (ref "P21") (pin "1") (pinfunction "1_1") (pintype "passive"))
      (node (ref "P22") (pin "1") (pinfunction "1_1") (pintype "passive"))
      (node (ref "P23") (pin "1") (pinfunction "1_1") (pintype "passive"))
      (node (ref "P24") (pin "1") (pinfunction "1_1") (pintype "passive"))
      (node (ref "P25") (pin "1") (pinfunction "1_1") (pintype "passive"))
      (node (ref "P26") (pin "1") (pinfunction "1_1") (pintype "passive"))
      (node (ref "P27") (pin "1") (pinfunction "1_1") (pintype "passive"))
      (node (ref "P28") (pin "1") (pinfunction "1_1") (pintype "passive"))
      (node (ref "P3") (pin "1") (pinfunction "1_1") (pintype "passive"))
      (node (ref "P4") (pin "1") (pinfunction "1_1") (pintype "passive"))
      (node (ref "P5") (pin "1") (pinfunction "1_1") (pintype "passive"))
      (node (ref "P6") (pin "1") (pinfunction "1_1") (pintype "passive"))
      (node (ref "P7") (pin "1") (pinfunction "1_1") (pintype "passive"))
      (node (ref "P8") (pin "1") (pinfunction "1_1") (pintype "passive"))
      (node (ref "P9") (pin "1") (pinfunction "1_1") (pintype "passive"))
      (node (ref "U201") (pin "11") (pinfunction "E_11") (pintype "passive"))
      (node (ref "U201") (pin "13") (pinfunction "E_13") (pintype "passive"))
      (node (ref "U201") (pin "15") (pinfunction "E_15") (pintype "passive"))
      (node (ref "U201") (pin "9") (pinfunction "E_9") (pintype "passive"))
      (node (ref "U202") (pin "11") (pinfunction "E_11") (pintype "passive"))
      (node (ref "U202") (pin "13") (pinfunction "E_13") (pintype "passive"))
      (node (ref "U202") (pin "15") (pinfunction "E_15") (pintype "passive"))
      (node (ref "U202") (pin "9") (pinfunction "E_9") (pintype "passive"))
      (node (ref "U203") (pin "11") (pinfunction "E_11") (pintype "passive"))
      (node (ref "U203") (pin "13") (pinfunction "E_13") (pintype "passive"))
      (node (ref "U203") (pin "15") (pinfunction "E_15") (pintype "passive"))
      (node (ref "U203") (pin "9") (pinfunction "E_9") (pintype "passive"))
      (node (ref "U204") (pin "11") (pinfunction "E_11") (pintype "passive"))
      (node (ref "U204") (pin "13") (pinfunction "E_13") (pintype "passive"))
      (node (ref "U204") (pin "15") (pinfunction "E_15") (pintype "passive"))
      (node (ref "U204") (pin "9") (pinfunction "E_9") (pintype "passive"))
      (node (ref "U205") (pin "11") (pinfunction "E_11") (pintype "passive"))
      (node (ref "U205") (pin "13") (pinfunction "E_13") (pintype "passive"))
      (node (ref "U205") (pin "15") (pinfunction "E_15") (pintype "passive"))
      (node (ref "U205") (pin "9") (pinfunction "E_9") (pintype "passive"))
      (node (ref "U206") (pin "11") (pinfunction "E_11") (pintype "passive"))
      (node (ref "U206") (pin "13") (pinfunction "E_13") (pintype "passive"))
      (node (ref "U206") (pin "15") (pinfunction "E_15") (pintype "passive"))
      (node (ref "U206") (pin "9") (pinfunction "E_9") (pintype "passive"))
      (node (ref "U207") (pin "11") (pinfunction "E_11") (pintype "passive"))
      (node (ref "U207") (pin "13") (pinfunction "E_13") (pintype "passive"))
      (node (ref "U207") (pin "15") (pinfunction "E_15") (pintype "passive"))
      (node (ref "U207") (pin "9") (pinfunction "E_9") (pintype "passive"))
    )
    (net (code "58") (name "GND_MCU") (class "Default")
      (node (ref "P1") (pin "4") (pinfunction "4_4") (pintype "passive"))
      (node (ref "P10") (pin "4") (pinfunction "4_4") (pintype "passive"))
      (node (ref "P11") (pin "4") (pinfunction "4_4") (pintype "passive"))
      (node (ref "P12") (pin "4") (pinfunction "4_4") (pintype "passive"))
      (node (ref "P13") (pin "4") (pinfunction "4_4") (pintype "passive"))
      (node (ref "P14") (pin "4") (pinfunction "4_4") (pintype "passive"))
      (node (ref "P15") (pin "4") (pinfunction "4_4") (pintype "passive"))
      (node (ref "P16") (pin "4") (pinfunction "4_4") (pintype "passive"))
      (node (ref "P17") (pin "4") (pinfunction "4_4") (pintype "passive"))
      (node (ref "P18") (pin "4") (pinfunction "4_4") (pintype "passive"))
      (node (ref "P19") (pin "4") (pinfunction "4_4") (pintype "passive"))
      (node (ref "P2") (pin "4") (pinfunction "4_4") (pintype "passive"))
      (node (ref "P20") (pin "4") (pinfunction "4_4") (pintype "passive"))
      (node (ref "P21") (pin "4") (pinfunction "4_4") (pintype "passive"))
      (node (ref "P22") (pin "4") (pinfunction "4_4") (pintype "passive"))
      (node (ref "P23") (pin "4") (pinfunction "4_4") (pintype "passive"))
      (node (ref "P24") (pin "4") (pinfunction "4_4") (pintype "passive"))
      (node (ref "P25") (pin "4") (pinfunction "4_4") (pintype "passive"))
      (node (ref "P26") (pin "4") (pinfunction "4_4") (pintype "passive"))
      (node (ref "P27") (pin "4") (pinfunction "4_4") (pintype "passive"))
      (node (ref "P28") (pin "4") (pinfunction "4_4") (pintype "passive"))
      (node (ref "P3") (pin "4") (pinfunction "4_4") (pintype "passive"))
      (node (ref "P4") (pin "4") (pinfunction "4_4") (pintype "passive"))
      (node (ref "P5") (pin "4") (pinfunction "4_4") (pintype "passive"))
      (node (ref "P6") (pin "4") (pinfunction "4_4") (pintype "passive"))
      (node (ref "P7") (pin "4") (pinfunction "4_4") (pintype "passive"))
      (node (ref "P8") (pin "4") (pinfunction "4_4") (pintype "passive"))
      (node (ref "P9") (pin "4") (pinfunction "4_4") (pintype "passive"))
    )
    (net (code "59") (name "Net-(D9-Pad2)") (class "Default")
      (node (ref "D9") (pin "2") (pintype "passive"))
      (node (ref "P5") (pin "2") (pinfunction "2_2") (pintype "passive"))
      (node (ref "U16") (pin "7") (pinfunction "D2_7") (pintype "passive"))
      (node (ref "U16") (pin "8") (pinfunction "D2_8") (pintype "passive"))
    )
    (net (code "60") (name "Net-(D10-Pad2)") (class "Default")
      (node (ref "D10") (pin "2") (pintype "passive"))
      (node (ref "P7") (pin "2") (pinfunction "2_2") (pintype "passive"))
      (node (ref "U17") (pin "7") (pinfunction "D2_7") (pintype "passive"))
      (node (ref "U17") (pin "8") (pinfunction "D2_8") (pintype "passive"))
    )
    (net (code "61") (name "Net-(D11-Pad2)") (class "Default")
      (node (ref "D11") (pin "2") (pintype "passive"))
      (node (ref "P9") (pin "2") (pinfunction "2_2") (pintype "passive"))
      (node (ref "U18") (pin "7") (pinfunction "D2_7") (pintype "passive"))
      (node (ref "U18") (pin "8") (pinfunction "D2_8") (pintype "passive"))
    )
    (net (code "62") (name "Net-(D12-Pad2)") (class "Default")
      (node (ref "D12") (pin "2") (pintype "passive"))
      (node (ref "P6") (pin "2") (pinfunction "2_2") (pintype "passive"))
      (node (ref "U16") (pin "5") (pinfunction "D1_5") (pintype "passive"))
      (node (ref "U16") (pin "6") (pinfunction "D1_6") (pintype "passive"))
    )
    (net (code "63") (name "Net-(D13-Pad2)") (class "Default")
      (node (ref "D13") (pin "2") (pintype "passive"))
      (node (ref "P8") (pin "2") (pinfunction "2_2") (pintype "passive"))
      (node (ref "U17") (pin "5") (pinfunction "D1_5") (pintype "passive"))
      (node (ref "U17") (pin "6") (pinfunction "D1_6") (pintype "passive"))
    )
    (net (code "64") (name "Net-(D14-Pad2)") (class "Default")
      (node (ref "D14") (pin "2") (pintype "passive"))
      (node (ref "P10") (pin "2") (pinfunction "2_2") (pintype "passive"))
      (node (ref "U18") (pin "5") (pinfunction "D1_5") (pintype "passive"))
      (node (ref "U18") (pin "6") (pinfunction "D1_6") (pintype "passive"))
    )
    (net (code "65") (name "Net-(D15-Pad2)") (class "Default")
      (node (ref "D15") (pin "2") (pintype "passive"))
      (node (ref "P11") (pin "2") (pinfunction "2_2") (pintype "passive"))
      (node (ref "U31") (pin "7") (pinfunction "D2_7") (pintype "passive"))
      (node (ref "U31") (pin "8") (pinfunction "D2_8") (pintype "passive"))
    )
    (net (code "66") (name "Net-(D16-Pad2)") (class "Default")
      (node (ref "D16") (pin "2") (pintype "passive"))
      (node (ref "P13") (pin "2") (pinfunction "2_2") (pintype "passive"))
      (node (ref "U32") (pin "7") (pinfunction "D2_7") (pintype "passive"))
      (node (ref "U32") (pin "8") (pinfunction "D2_8") (pintype "passive"))
    )
    (net (code "67") (name "Net-(D17-Pad2)") (class "Default")
      (node (ref "D17") (pin "2") (pintype "passive"))
      (node (ref "P15") (pin "2") (pinfunction "2_2") (pintype "passive"))
      (node (ref "U33") (pin "7") (pinfunction "D2_7") (pintype "passive"))
      (node (ref "U33") (pin "8") (pinfunction "D2_8") (pintype "passive"))
    )
    (net (code "68") (name "Net-(D18-Pad2)") (class "Default")
      (node (ref "D18") (pin "2") (pintype "passive"))
      (node (ref "P12") (pin "2") (pinfunction "2_2") (pintype "passive"))
      (node (ref "U31") (pin "5") (pinfunction "D1_5") (pintype "passive"))
      (node (ref "U31") (pin "6") (pinfunction "D1_6") (pintype "passive"))
    )
    (net (code "69") (name "Net-(D19-Pad2)") (class "Default")
      (node (ref "D19") (pin "2") (pintype "passive"))
      (node (ref "P14") (pin "2") (pinfunction "2_2") (pintype "passive"))
      (node (ref "U32") (pin "5") (pinfunction "D1_5") (pintype "passive"))
      (node (ref "U32") (pin "6") (pinfunction "D1_6") (pintype "passive"))
    )
    (net (code "70") (name "Net-(D20-Pad2)") (class "Default")
      (node (ref "D20") (pin "2") (pintype "passive"))
      (node (ref "P16") (pin "2") (pinfunction "2_2") (pintype "passive"))
      (node (ref "U33") (pin "5") (pinfunction "D1_5") (pintype "passive"))
      (node (ref "U33") (pin "6") (pinfunction "D1_6") (pintype "passive"))
    )
    (net (code "71") (name "Net-(D21-Pad2)") (class "Default")
      (node (ref "D21") (pin "2") (pintype "passive"))
      (node (ref "P17") (pin "2") (pinfunction "2_2") (pintype "passive"))
      (node (ref "U46") (pin "7") (pinfunction "D2_7") (pintype "passive"))
      (node (ref "U46") (pin "8") (pinfunction "D2_8") (pintype "passive"))
    )
    (net (code "72") (name "Net-(D22-Pad2)") (class "Default")
      (node (ref "D22") (pin "2") (pintype "passive"))
      (node (ref "P19") (pin "2") (pinfunction "2_2") (pintype "passive"))
      (node (ref "U47") (pin "7") (pinfunction "D2_7") (pintype "passive"))
      (node (ref "U47") (pin "8") (pinfunction "D2_8") (pintype "passive"))
    )
    (net (code "73") (name "Net-(D23-Pad2)") (class "Default")
      (node (ref "D23") (pin "2") (pintype "passive"))
      (node (ref "P21") (pin "2") (pinfunction "2_2") (pintype "passive"))
      (node (ref "U48") (pin "7") (pinfunction "D2_7") (pintype "passive"))
      (node (ref "U48") (pin "8") (pinfunction "D2_8") (pintype "passive"))
    )
    (net (code "74") (name "Net-(D24-Pad2)") (class "Default")
      (node (ref "D24") (pin "2") (pintype "passive"))
      (node (ref "P18") (pin "2") (pinfunction "2_2") (pintype "passive"))
      (node (ref "U46") (pin "5") (pinfunction "D1_5") (pintype "passive"))
      (node (ref "U46") (pin "6") (pinfunction "D1_6") (pintype "passive"))
    )
    (net (code "75") (name "Net-(D25-Pad2)") (class "Default")
      (node (ref "D25") (pin "2") (pintype "passive"))
      (node (ref "P20") (pin "2") (pinfunction "2_2") (pintype "passive"))
      (node (ref "U47") (pin "5") (pinfunction "D1_5") (pintype "passive"))
      (node (ref "U47") (pin "6") (pinfunction "D1_6") (pintype "passive"))
    )
    (net (code "76") (name "Net-(D26-Pad2)") (class "Default")
      (node (ref "D26") (pin "2") (pintype "passive"))
      (node (ref "P22") (pin "2") (pinfunction "2_2") (pintype "passive"))
      (node (ref "U48") (pin "5") (pinfunction "D1_5") (pintype "passive"))
      (node (ref "U48") (pin "6") (pinfunction "D1_6") (pintype "passive"))
    )
    (net (code "77") (name "Net-(D27-Pad2)") (class "Default")
      (node (ref "D27") (pin "2") (pintype "passive"))
      (node (ref "P23") (pin "2") (pinfunction "2_2") (pintype "passive"))
      (node (ref "U61") (pin "7") (pinfunction "D2_7") (pintype "passive"))
      (node (ref "U61") (pin "8") (pinfunction "D2_8") (pintype "passive"))
    )
    (net (code "78") (name "Net-(D28-Pad2)") (class "Default")
      (node (ref "D28") (pin "2") (pintype "passive"))
      (node (ref "P25") (pin "2") (pinfunction "2_2") (pintype "passive"))
      (node (ref "U62") (pin "7") (pinfunction "D2_7") (pintype "passive"))
      (node (ref "U62") (pin "8") (pinfunction "D2_8") (pintype "passive"))
    )
    (net (code "79") (name "Net-(D29-Pad2)") (class "Default")
      (node (ref "D29") (pin "2") (pintype "passive"))
      (node (ref "P27") (pin "2") (pinfunction "2_2") (pintype "passive"))
      (node (ref "U63") (pin "7") (pinfunction "D2_7") (pintype "passive"))
      (node (ref "U63") (pin "8") (pinfunction "D2_8") (pintype "passive"))
    )
    (net (code "80") (name "Net-(D30-Pad2)") (class "Default")
      (node (ref "D30") (pin "2") (pintype "passive"))
      (node (ref "P24") (pin "2") (pinfunction "2_2") (pintype "passive"))
      (node (ref "U61") (pin "5") (pinfunction "D1_5") (pintype "passive"))
      (node (ref "U61") (pin "6") (pinfunction "D1_6") (pintype "passive"))
    )
    (net (code "81") (name "Net-(D31-Pad2)") (class "Default")
      (node (ref "D31") (pin "2") (pintype "passive"))
      (node (ref "P26") (pin "2") (pinfunction "2_2") (pintype "passive"))
      (node (ref "U62") (pin "5") (pinfunction "D1_5") (pintype "passive"))
      (node (ref "U62") (pin "6") (pinfunction "D1_6") (pintype "passive"))
    )
    (net (code "82") (name "Net-(D32-Pad2)") (class "Default")
      (node (ref "D32") (pin "2") (pintype "passive"))
      (node (ref "P28") (pin "2") (pinfunction "2_2") (pintype "passive"))
      (node (ref "U63") (pin "5") (pinfunction "D1_5") (pintype "passive"))
      (node (ref "U63") (pin "6") (pinfunction "D1_6") (pintype "passive"))
    )
    (net (code "83") (name "Net-(D33-Pad2)") (class "Default")
      (node (ref "D33") (pin "2") (pintype "passive"))
      (node (ref "P1") (pin "2") (pinfunction "2_2") (pintype "passive"))
      (node (ref "U74") (pin "7") (pinfunction "D2_7") (pintype "passive"))
      (node (ref "U74") (pin "8") (pinfunction "D2_8") (pintype "passive"))
    )
    (net (code "84") (name "Net-(D34-Pad2)") (class "Default")
      (node (ref "D34") (pin "2") (pintype "passive"))
      (node (ref "P3") (pin "2") (pinfunction "2_2") (pintype "passive"))
      (node (ref "U75") (pin "7") (pinfunction "D2_7") (pintype "passive"))
      (node (ref "U75") (pin "8") (pinfunction "D2_8") (pintype "passive"))
    )
    (net (code "85") (name "Net-(D35-Pad2)") (class "Default")
      (node (ref "D35") (pin "2") (pintype "passive"))
      (node (ref "P2") (pin "2") (pinfunction "2_2") (pintype "passive"))
      (node (ref "U74") (pin "5") (pinfunction "D1_5") (pintype "passive"))
      (node (ref "U74") (pin "6") (pinfunction "D1_6") (pintype "passive"))
    )
    (net (code "86") (name "Net-(D36-Pad2)") (class "Default")
      (node (ref "D36") (pin "2") (pintype "passive"))
      (node (ref "P4") (pin "2") (pinfunction "2_2") (pintype "passive"))
      (node (ref "U75") (pin "5") (pinfunction "D1_5") (pintype "passive"))
      (node (ref "U75") (pin "6") (pinfunction "D1_6") (pintype "passive"))
    )
    (net (code "87") (name "Net-(U16-G1)") (class "Default")
      (node (ref "R38") (pin "1") (pinfunction "1_1") (pintype "passive"))
      (node (ref "R41") (pin "2") (pinfunction "2_2") (pintype "passive"))
      (node (ref "U16") (pin "4") (pinfunction "G1_4") (pintype "passive"))
    )
    (net (code "88") (name "Net-(U16-G2)") (class "Default")
      (node (ref "R29") (pin "1") (pinfunction "1_1") (pintype "passive"))
      (node (ref "R32") (pin "2") (pinfunction "2_2") (pintype "passive"))
      (node (ref "U16") (pin "2") (pinfunction "G2_2") (pintype "passive"))
    )
    (net (code "89") (name "Net-(U17-G1)") (class "Default")
      (node (ref "R39") (pin "1") (pinfunction "1_1") (pintype "passive"))
      (node (ref "R42") (pin "2") (pinfunction "2_2") (pintype "passive"))
      (node (ref "U17") (pin "4") (pinfunction "G1_4") (pintype "passive"))
    )
    (net (code "90") (name "Net-(U17-G2)") (class "Default")
      (node (ref "R30") (pin "1") (pinfunction "1_1") (pintype "passive"))
      (node (ref "R33") (pin "2") (pinfunction "2_2") (pintype "passive"))
      (node (ref "U17") (pin "2") (pinfunction "G2_2") (pintype "passive"))
    )
    (net (code "91") (name "Net-(U18-G1)") (class "Default")
      (node (ref "R40") (pin "1") (pinfunction "1_1") (pintype "passive"))
      (node (ref "R43") (pin "2") (pinfunction "2_2") (pintype "passive"))
      (node (ref "U18") (pin "4") (pinfunction "G1_4") (pintype "passive"))
    )
    (net (code "92") (name "Net-(U18-G2)") (class "Default")
      (node (ref "R31") (pin "1") (pinfunction "1_1") (pintype "passive"))
      (node (ref "R34") (pin "2") (pinfunction "2_2") (pintype "passive"))
      (node (ref "U18") (pin "2") (pinfunction "G2_2") (pintype "passive"))
    )
    (net (code "93") (name "Net-(U31-G1)") (class "Default")
      (node (ref "R56") (pin "1") (pinfunction "1_1") (pintype "passive"))
      (node (ref "R59") (pin "2") (pinfunction "2_2") (pintype "passive"))
      (node (ref "U31") (pin "4") (pinfunction "G1_4") (pintype "passive"))
    )
    (net (code "94") (name "Net-(U31-G2)") (class "Default")
      (node (ref "R47") (pin "1") (pinfunction "1_1") (pintype "passive"))
      (node (ref "R50") (pin "2") (pinfunction "2_2") (pintype "passive"))
      (node (ref "U31") (pin "2") (pinfunction "G2_2") (pintype "passive"))
    )
    (net (code "95") (name "Net-(U32-G1)") (class "Default")
      (node (ref "R57") (pin "1") (pinfunction "1_1") (pintype "passive"))
      (node (ref "R60") (pin "2") (pinfunction "2_2") (pintype "passive"))
      (node (ref "U32") (pin "4") (pinfunction "G1_4") (pintype "passive"))
    )
    (net (code "96") (name "Net-(U32-G2)") (class "Default")
      (node (ref "R48") (pin "1") (pinfunction "1_1") (pintype "passive"))
      (node (ref "R51") (pin "2") (pinfunction "2_2") (pintype "passive"))
      (node (ref "U32") (pin "2") (pinfunction "G2_2") (pintype "passive"))
    )
    (net (code "97") (name "Net-(U33-G1)") (class "Default")
      (node (ref "R58") (pin "1") (pinfunction "1_1") (pintype "passive"))
      (node (ref "R61") (pin "2") (pinfunction "2_2") (pintype "passive"))
      (node (ref "U33") (pin "4") (pinfunction "G1_4") (pintype "passive"))
    )
    (net (code "98") (name "Net-(U33-G2)") (class "Default")
      (node (ref "R49") (pin "1") (pinfunction "1_1") (pintype "passive"))
      (node (ref "R52") (pin "2") (pinfunction "2_2") (pintype "passive"))
      (node (ref "U33") (pin "2") (pinfunction "G2_2") (pintype "passive"))
    )
    (net (code "99") (name "Net-(U46-G1)") (class "Default")
      (node (ref "R74") (pin "1") (pinfunction "1_1") (pintype "passive"))
      (node (ref "R77") (pin "2") (pinfunction "2_2") (pintype "passive"))
      (node (ref "U46") (pin "4") (pinfunction "G1_4") (pintype "passive"))
    )
    (net (code "100") (name "Net-(U46-G2)") (class "Default")
      (node (ref "R65") (pin "1") (pinfunction "1_1") (pintype "passive"))
      (node (ref "R68") (pin "2") (pinfunction "2_2") (pintype "passive"))
      (node (ref "U46") (pin "2") (pinfunction "G2_2") (pintype "passive"))
    )
    (net (code "101") (name "Net-(U47-G1)") (class "Default")
      (node (ref "R75") (pin "1") (pinfunction "1_1") (pintype "passive"))
      (node (ref "R78") (pin "2") (pinfunction "2_2") (pintype "passive"))
      (node (ref "U47") (pin "4") (pinfunction "G1_4") (pintype "passive"))
    )
    (net (code "102") (name "Net-(U47-G2)") (class "Default")
      (node (ref "R66") (pin "1") (pinfunction "1_1") (pintype "passive"))
      (node (ref "R69") (pin "2") (pinfunction "2_2") (pintype "passive"))
      (node (ref "U47") (pin "2") (pinfunction "G2_2") (pintype "passive"))
    )
    (net (code "103") (name "Net-(U48-G1)") (class "Default")
      (node (ref "R76") (pin "1") (pinfunction "1_1") (pintype "passive"))
      (node (ref "R79") (pin "2") (pinfunction "2_2") (pintype "passive"))
      (node (ref "U48") (pin "4") (pinfunction "G1_4") (pintype "passive"))
    )
    (net (code "104") (name "Net-(U48-G2)") (class "Default")
      (node (ref "R67") (pin "1") (pinfunction "1_1") (pintype "passive"))
      (node (ref "R70") (pin "2") (pinfunction "2_2") (pintype "passive"))
      (node (ref "U48") (pin "2") (pinfunction "G2_2") (pintype "passive"))
    )
    (net (code "105") (name "Net-(U61-G1)") (class "Default")
      (node (ref "R92") (pin "1") (pinfunction "1_1") (pintype "passive"))
      (node (ref "R95") (pin "2") (pinfunction "2_2") (pintype "passive"))
      (node (ref "U61") (pin "4") (pinfunction "G1_4") (pintype "passive"))
    )
    (net (code "106") (name "Net-(U61-G2)") (class "Default")
      (node (ref "R83") (pin "1") (pinfunction "1_1") (pintype "passive"))
      (node (ref "R86") (pin "2") (pinfunction "2_2") (pintype "passive"))
      (node (ref "U61") (pin "2") (pinfunction "G2_2") (pintype "passive"))
    )
    (net (code "107") (name "Net-(U62-G1)") (class "Default")
      (node (ref "R93") (pin "1") (pinfunction "1_1") (pintype "passive"))
      (node (ref "R96") (pin "2") (pinfunction "2_2") (pintype "passive"))
      (node (ref "U62") (pin "4") (pinfunction "G1_4") (pintype "passive"))
    )
    (net (code "108") (name "Net-(U62-G2)") (class "Default")
      (node (ref "R84") (pin "1") (pinfunction "1_1") (pintype "passive"))
      (node (ref "R87") (pin "2") (pinfunction "2_2") (pintype "passive"))
      (node (ref "U62") (pin "2") (pinfunction "G2_2") (pintype "passive"))
    )
    (net (code "109") (name "Net-(U63-G1)") (class "Default")
      (node (ref "R94") (pin "1") (pinfunction "1_1") (pintype "passive"))
      (node (ref "R97") (pin "2") (pinfunction "2_2") (pintype "passive"))
      (node (ref "U63") (pin "4") (pinfunction "G1_4") (pintype "passive"))
    )
    (net (code "110") (name "Net-(U63-G2)") (class "Default")
      (node (ref "R85") (pin "1") (pinfunction "1_1") (pintype "passive"))
      (node (ref "R88") (pin "2") (pinfunction "2_2") (pintype "passive"))
      (node (ref "U63") (pin "2") (pinfunction "G2_2") (pintype "passive"))
    )
    (net (code "111") (name "Net-(U74-G1)") (class "Default")
      (node (ref "R107") (pin "1") (pinfunction "1_1") (pintype "passive"))
      (node (ref "R109") (pin "2") (pinfunction "2_2") (pintype "passive"))
      (node (ref "U74") (pin "4") (pinfunction "G1_4") (pintype "passive"))
    )
    (net (code "112") (name "Net-(U74-G2)") (class "Default")
      (node (ref "R101") (pin "1") (pinfunction "1_1") (pintype "passive"))
      (node (ref "R103") (pin "2") (pinfunction "2_2") (pintype "passive"))
      (node (ref "U74") (pin "2") (pinfunction "G2_2") (pintype "passive"))
    )
    (net (code "113") (name "Net-(U75-G1)") (class "Default")
      (node (ref "R108") (pin "1") (pinfunction "1_1") (pintype "passive"))
      (node (ref "R110") (pin "2") (pinfunction "2_2") (pintype "passive"))
      (node (ref "U75") (pin "4") (pinfunction "G1_4") (pintype "passive"))
    )
    (net (code "114") (name "Net-(U75-G2)") (class "Default")
      (node (ref "R102") (pin "1") (pinfunction "1_1") (pintype "passive"))
      (node (ref "R104") (pin "2") (pinfunction "2_2") (pintype "passive"))
      (node (ref "U75") (pin "2") (pinfunction "G2_2") (pintype "passive"))
    )
    (net (code "115") (name "Net-(U201A-C)") (class "Default")
      (node (ref "R103") (pin "1") (pinfunction "1_1") (pintype "passive"))
      (node (ref "U201") (pin "16") (pinfunction "C_16") (pintype "passive"))
    )
    (net (code "116") (name "Net-(U201A-K)") (class "Default")
      (node (ref "R105") (pin "2") (pinfunction "2_2") (pintype "passive"))
      (node (ref "U201") (pin "2") (pinfunction "K_2") (pintype "passive"))
    )
    (net (code "117") (name "Net-(U201B-C)") (class "Default")
      (node (ref "R109") (pin "1") (pinfunction "1_1") (pintype "passive"))
      (node (ref "U201") (pin "14") (pinfunction "C_14") (pintype "passive"))
    )
    (net (code "118") (name "Net-(U201B-K)") (class "Default")
      (node (ref "R111") (pin "2") (pinfunction "2_2") (pintype "passive"))
      (node (ref "U201") (pin "4") (pinfunction "K_4") (pintype "passive"))
    )
    (net (code "119") (name "Net-(U201C-C)") (class "Default")
      (node (ref "R104") (pin "1") (pinfunction "1_1") (pintype "passive"))
      (node (ref "U201") (pin "12") (pinfunction "C_12") (pintype "passive"))
    )
    (net (code "120") (name "Net-(U201C-K)") (class "Default")
      (node (ref "R106") (pin "2") (pinfunction "2_2") (pintype "passive"))
      (node (ref "U201") (pin "6") (pinfunction "K_6") (pintype "passive"))
    )
    (net (code "121") (name "Net-(U201D-C)") (class "Default")
      (node (ref "R110") (pin "1") (pinfunction "1_1") (pintype "passive"))
      (node (ref "U201") (pin "10") (pinfunction "C_10") (pintype "passive"))
    )
    (net (code "122") (name "Net-(U201D-K)") (class "Default")
      (node (ref "R112") (pin "2") (pinfunction "2_2") (pintype "passive"))
      (node (ref "U201") (pin "8") (pinfunction "K_8") (pintype "passive"))
    )
    (net (code "123") (name "Net-(U202A-C)") (class "Default")
      (node (ref "R32") (pin "1") (pinfunction "1_1") (pintype "passive"))
      (node (ref "U202") (pin "16") (pinfunction "C_16") (pintype "passive"))
    )
    (net (code "124") (name "Net-(U202A-K)") (class "Default")
      (node (ref "R35") (pin "2") (pinfunction "2_2") (pintype "passive"))
      (node (ref "U202") (pin "2") (pinfunction "K_2") (pintype "passive"))
    )
    (net (code "125") (name "Net-(U202B-C)") (class "Default")
      (node (ref "R41") (pin "1") (pinfunction "1_1") (pintype "passive"))
      (node (ref "U202") (pin "14") (pinfunction "C_14") (pintype "passive"))
    )
    (net (code "126") (name "Net-(U202B-K)") (class "Default")
      (node (ref "R44") (pin "2") (pinfunction "2_2") (pintype "passive"))
      (node (ref "U202") (pin "4") (pinfunction "K_4") (pintype "passive"))
    )
    (net (code "127") (name "Net-(U202C-C)") (class "Default")
      (node (ref "R33") (pin "1") (pinfunction "1_1") (pintype "passive"))
      (node (ref "U202") (pin "12") (pinfunction "C_12") (pintype "passive"))
    )
    (net (code "128") (name "Net-(U202C-K)") (class "Default")
      (node (ref "R36") (pin "2") (pinfunction "2_2") (pintype "passive"))
      (node (ref "U202") (pin "6") (pinfunction "K_6") (pintype "passive"))
    )
    (net (code "129") (name "Net-(U202D-C)") (class "Default")
      (node (ref "R42") (pin "1") (pinfunction "1_1") (pintype "passive"))
      (node (ref "U202") (pin "10") (pinfunction "C_10") (pintype "passive"))
    )
    (net (code "130") (name "Net-(U202D-K)") (class "Default")
      (node (ref "R45") (pin "2") (pinfunction "2_2") (pintype "passive"))
      (node (ref "U202") (pin "8") (pinfunction "K_8") (pintype "passive"))
    )
    (net (code "131") (name "Net-(U203A-C)") (class "Default")
      (node (ref "R34") (pin "1") (pinfunction "1_1") (pintype "passive"))
      (node (ref "U203") (pin "16") (pinfunction "C_16") (pintype "passive"))
    )
    (net (code "132") (name "Net-(U203A-K)") (class "Default")
      (node (ref "R37") (pin "2") (pinfunction "2_2") (pintype "passive"))
      (node (ref "U203") (pin "2") (pinfunction "K_2") (pintype "passive"))
    )
    (net (code "133") (name "Net-(U203B-C)") (class "Default")
      (node (ref "R43") (pin "1") (pinfunction "1_1") (pintype "passive"))
      (node (ref "U203") (pin "14") (pinfunction "C_14") (pintype "passive"))
    )
    (net (code "134") (name "Net-(U203B-K)") (class "Default")
      (node (ref "R46") (pin "2") (pinfunction "2_2") (pintype "passive"))
      (node (ref "U203") (pin "4") (pinfunction "K_4") (pintype "passive"))
    )
    (net (code "135") (name "Net-(U203C-C)") (class "Default")
      (node (ref "R50") (pin "1") (pinfunction "1_1") (pintype "passive"))
      (node (ref "U203") (pin "12") (pinfunction "C_12") (pintype "passive"))
    )
    (net (code "136") (name "Net-(U203C-K)") (class "Default")
      (node (ref "R53") (pin "2") (pinfunction "2_2") (pintype "passive"))
      (node (ref "U203") (pin "6") (pinfunction "K_6") (pintype "passive"))
    )
    (net (code "137") (name "Net-(U203D-C)") (class "Default")
      (node (ref "R59") (pin "1") (pinfunction "1_1") (pintype "passive"))
      (node (ref "U203") (pin "10") (pinfunction "C_10") (pintype "passive"))
    )
    (net (code "138") (name "Net-(U203D-K)") (class "Default")
      (node (ref "R62") (pin "2") (pinfunction "2_2") (pintype "passive"))
      (node (ref "U203") (pin "8") (pinfunction "K_8") (pintype "passive"))
    )
    (net (code "139") (name "Net-(U204A-C)") (class "Default")
      (node (ref "R51") (pin "1") (pinfunction "1_1") (pintype "passive"))
      (node (ref "U204") (pin "16") (pinfunction "C_16") (pintype "passive"))
    )
    (net (code "140") (name "Net-(U204A-K)") (class "Default")
      (node (ref "R54") (pin "2") (pinfunction "2_2") (pintype "passive"))
      (node (ref "U204") (pin "2") (pinfunction "K_2") (pintype "passive"))
    )
    (net (code "141") (name "Net-(U204B-C)") (class "Default")
      (node (ref "R60") (pin "1") (pinfunction "1_1") (pintype "passive"))
      (node (ref "U204") (pin "14") (pinfunction "C_14") (pintype "passive"))
    )
    (net (code "142") (name "Net-(U204B-K)") (class "Default")
      (node (ref "R63") (pin "2") (pinfunction "2_2") (pintype "passive"))
      (node (ref "U204") (pin "4") (pinfunction "K_4") (pintype "passive"))
    )
    (net (code "143") (name "Net-(U204C-C)") (class "Default")
      (node (ref "R52") (pin "1") (pinfunction "1_1") (pintype "passive"))
      (node (ref "U204") (pin "12") (pinfunction "C_12") (pintype "passive"))
    )
    (net (code "144") (name "Net-(U204C-K)") (class "Default")
      (node (ref "R55") (pin "2") (pinfunction "2_2") (pintype "passive"))
      (node (ref "U204") (pin "6") (pinfunction "K_6") (pintype "passive"))
    )
    (net (code "145") (name "Net-(U204D-C)") (class "Default")
      (node (ref "R61") (pin "1") (pinfunction "1_1") (pintype "passive"))
      (node (ref "U204") (pin "10") (pinfunction "C_10") (pintype "passive"))
    )
    (net (code "146") (name "Net-(U204D-K)") (class "Default")
      (node (ref "R64") (pin "2") (pinfunction "2_2") (pintype "passive"))
      (node (ref "U204") (pin "8") (pinfunction "K_8") (pintype "passive"))
    )
    (net (code "147") (name "Net-(U205A-C)") (class "Default")
      (node (ref "R68") (pin "1") (pinfunction "1_1") (pintype "passive"))
      (node (ref "U205") (pin "16") (pinfunction "C_16") (pintype "passive"))
    )
    (net (code "148") (name "Net-(U205A-K)") (class "Default")
      (node (ref "R71") (pin "2") (pinfunction "2_2") (pintype "passive"))
      (node (ref "U205") (pin "2") (pinfunction "K_2") (pintype "passive"))
    )
    (net (code "149") (name "Net-(U205B-C)") (class "Default")
      (node (ref "R77") (pin "1") (pinfunction "1_1") (pintype "passive"))
      (node (ref "U205") (pin "14") (pinfunction "C_14") (pintype "passive"))
    )
    (net (code "150") (name "Net-(U205B-K)") (class "Default")
      (node (ref "R80") (pin "2") (pinfunction "2_2") (pintype "passive"))
      (node (ref "U205") (pin "4") (pinfunction "K_4") (pintype "passive"))
    )
    (net (code "151") (name "Net-(U205C-C)") (class "Default")
      (node (ref "R69") (pin "1") (pinfunction "1_1") (pintype "passive"))
      (node (ref "U205") (pin "12") (pinfunction "C_12") (pintype "passive"))
    )
    (net (code "152") (name "Net-(U205C-K)") (class "Default")
      (node (ref "R72") (pin "2") (pinfunction "2_2") (pintype "passive"))
      (node (ref "U205") (pin "6") (pinfunction "K_6") (pintype "passive"))
    )
    (net (code "153") (name "Net-(U205D-C)") (class "Default")
      (node (ref "R78") (pin "1") (pinfunction "1_1") (pintype "passive"))
      (node (ref "U205") (pin "10") (pinfunction "C_10") (pintype "passive"))
    )
    (net (code "154") (name "Net-(U205D-K)") (class "Default")
      (node (ref "R81") (pin "2") (pinfunction "2_2") (pintype "passive"))
      (node (ref "U205") (pin "8") (pinfunction "K_8") (pintype "passive"))
    )
    (net (code "155") (name "Net-(U206A-C)") (class "Default")
      (node (ref "R87") (pin "1") (pinfunction "1_1") (pintype "passive"))
      (node (ref "U206") (pin "16") (pinfunction "C_16") (pintype "passive"))
    )
    (net (code "156") (name "Net-(U206A-K)") (class "Default")
      (node (ref "R90") (pin "2") (pinfunction "2_2") (pintype "passive"))
      (node (ref "U206") (pin "2") (pinfunction "K_2") (pintype "passive"))
    )
    (net (code "157") (name "Net-(U206B-C)") (class "Default")
      (node (ref "R96") (pin "1") (pinfunction "1_1") (pintype "passive"))
      (node (ref "U206") (pin "14") (pinfunction "C_14") (pintype "passive"))
    )
    (net (code "158") (name "Net-(U206B-K)") (class "Default")
      (node (ref "R99") (pin "2") (pinfunction "2_2") (pintype "passive"))
      (node (ref "U206") (pin "4") (pinfunction "K_4") (pintype "passive"))
    )
    (net (code "159") (name "Net-(U206C-C)") (class "Default")
      (node (ref "R88") (pin "1") (pinfunction "1_1") (pintype "passive"))
      (node (ref "U206") (pin "12") (pinfunction "C_12") (pintype "passive"))
    )
    (net (code "160") (name "Net-(U206C-K)") (class "Default")
      (node (ref "R91") (pin "2") (pinfunction "2_2") (pintype "passive"))
      (node (ref "U206") (pin "6") (pinfunction "K_6") (pintype "passive"))
    )
    (net (code "161") (name "Net-(U206D-C)") (class "Default")
      (node (ref "R97") (pin "1") (pinfunction "1_1") (pintype "passive"))
      (node (ref "U206") (pin "10") (pinfunction "C_10") (pintype "passive"))
    )
    (net (code "162") (name "Net-(U206D-K)") (class "Default")
      (node (ref "R100") (pin "2") (pinfunction "2_2") (pintype "passive"))
      (node (ref "U206") (pin "8") (pinfunction "K_8") (pintype "passive"))
    )
    (net (code "163") (name "Net-(U207A-C)") (class "Default")
      (node (ref "R70") (pin "1") (pinfunction "1_1") (pintype "passive"))
      (node (ref "U207") (pin "16") (pinfunction "C_16") (pintype "passive"))
    )
    (net (code "164") (name "Net-(U207A-K)") (class "Default")
      (node (ref "R73") (pin "2") (pinfunction "2_2") (pintype "passive"))
      (node (ref "U207") (pin "2") (pinfunction "K_2") (pintype "passive"))
    )
    (net (code "165") (name "Net-(U207B-C)") (class "Default")
      (node (ref "R79") (pin "1") (pinfunction "1_1") (pintype "passive"))
      (node (ref "U207") (pin "14") (pinfunction "C_14") (pintype "passive"))
    )
    (net (code "166") (name "Net-(U207B-K)") (class "Default")
      (node (ref "R82") (pin "2") (pinfunction "2_2") (pintype "passive"))
      (node (ref "U207") (pin "4") (pinfunction "K_4") (pintype "passive"))
    )
    (net (code "167") (name "Net-(U207C-C)") (class "Default")
      (node (ref "R86") (pin "1") (pinfunction "1_1") (pintype "passive"))
      (node (ref "U207") (pin "12") (pinfunction "C_12") (pintype "passive"))
    )
    (net (code "168") (name "Net-(U207C-K)") (class "Default")
      (node (ref "R89") (pin "2") (pinfunction "2_2") (pintype "passive"))
      (node (ref "U207") (pin "6") (pinfunction "K_6") (pintype "passive"))
    )
    (net (code "169") (name "Net-(U207D-C)") (class "Default")
      (node (ref "R95") (pin "1") (pinfunction "1_1") (pintype "passive"))
      (node (ref "U207") (pin "10") (pinfunction "C_10") (pintype "passive"))
    )
    (net (code "170") (name "Net-(U207D-K)") (class "Default")
      (node (ref "R98") (pin "2") (pinfunction "2_2") (pintype "passive"))
      (node (ref "U207") (pin "8") (pinfunction "K_8") (pintype "passive"))
    )
    (net (code "171") (name "VCC3.3_MCU") (class "Default")
      (node (ref "U201") (pin "1") (pinfunction "A_1") (pintype "passive"))
      (node (ref "U201") (pin "3") (pinfunction "A_3") (pintype "passive"))
      (node (ref "U201") (pin "5") (pinfunction "A_5") (pintype "passive"))
      (node (ref "U201") (pin "7") (pinfunction "A_7") (pintype "passive"))
      (node (ref "U202") (pin "1") (pinfunction "A_1") (pintype "passive"))
      (node (ref "U202") (pin "3") (pinfunction "A_3") (pintype "passive"))
      (node (ref "U202") (pin "5") (pinfunction "A_5") (pintype "passive"))
      (node (ref "U202") (pin "7") (pinfunction "A_7") (pintype "passive"))
      (node (ref "U203") (pin "1") (pinfunction "A_1") (pintype "passive"))
      (node (ref "U203") (pin "3") (pinfunction "A_3") (pintype "passive"))
      (node (ref "U203") (pin "5") (pinfunction "A_5") (pintype "passive"))
      (node (ref "U203") (pin "7") (pinfunction "A_7") (pintype "passive"))
      (node (ref "U204") (pin "1") (pinfunction "A_1") (pintype "passive"))
      (node (ref "U204") (pin "3") (pinfunction "A_3") (pintype "passive"))
      (node (ref "U204") (pin "5") (pinfunction "A_5") (pintype "passive"))
      (node (ref "U204") (pin "7") (pinfunction "A_7") (pintype "passive"))
      (node (ref "U205") (pin "1") (pinfunction "A_1") (pintype "passive"))
      (node (ref "U205") (pin "3") (pinfunction "A_3") (pintype "passive"))
      (node (ref "U205") (pin "5") (pinfunction "A_5") (pintype "passive"))
      (node (ref "U205") (pin "7") (pinfunction "A_7") (pintype "passive"))
      (node (ref "U206") (pin "1") (pinfunction "A_1") (pintype "passive"))
      (node (ref "U206") (pin "3") (pinfunction "A_3") (pintype "passive"))
      (node (ref "U206") (pin "5") (pinfunction "A_5") (pintype "passive"))
      (node (ref "U206") (pin "7") (pinfunction "A_7") (pintype "passive"))
      (node (ref "U207") (pin "1") (pinfunction "A_1") (pintype "passive"))
      (node (ref "U207") (pin "3") (pinfunction "A_3") (pintype "passive"))
      (node (ref "U207") (pin "5") (pinfunction "A_5") (pintype "passive"))
      (node (ref "U207") (pin "7") (pinfunction "A_7") (pintype "passive"))
    )
    (net (code "172") (name "VCC12") (class "Default")
      (node (ref "R101") (pin "2") (pinfunction "2_2") (pintype "passive"))
      (node (ref "R102") (pin "2") (pinfunction "2_2") (pintype "passive"))
      (node (ref "R107") (pin "2") (pinfunction "2_2") (pintype "passive"))
      (node (ref "R108") (pin "2") (pinfunction "2_2") (pintype "passive"))
      (node (ref "R29") (pin "2") (pinfunction "2_2") (pintype "passive"))
      (node (ref "R30") (pin "2") (pinfunction "2_2") (pintype "passive"))
      (node (ref "R31") (pin "2") (pinfunction "2_2") (pintype "passive"))
      (node (ref "R38") (pin "2") (pinfunction "2_2") (pintype "passive"))
      (node (ref "R39") (pin "2") (pinfunction "2_2") (pintype "passive"))
      (node (ref "R40") (pin "2") (pinfunction "2_2") (pintype "passive"))
      (node (ref "R47") (pin "2") (pinfunction "2_2") (pintype "passive"))
      (node (ref "R48") (pin "2") (pinfunction "2_2") (pintype "passive"))
      (node (ref "R49") (pin "2") (pinfunction "2_2") (pintype "passive"))
      (node (ref "R56") (pin "2") (pinfunction "2_2") (pintype "passive"))
      (node (ref "R57") (pin "2") (pinfunction "2_2") (pintype "passive"))
      (node (ref "R58") (pin "2") (pinfunction "2_2") (pintype "passive"))
      (node (ref "R65") (pin "2") (pinfunction "2_2") (pintype "passive"))
      (node (ref "R66") (pin "2") (pinfunction "2_2") (pintype "passive"))
      (node (ref "R67") (pin "2") (pinfunction "2_2") (pintype "passive"))
      (node (ref "R74") (pin "2") (pinfunction "2_2") (pintype "passive"))
      (node (ref "R75") (pin "2") (pinfunction "2_2") (pintype "passive"))
      (node (ref "R76") (pin "2") (pinfunction "2_2") (pintype "passive"))
      (node (ref "R83") (pin "2") (pinfunction "2_2") (pintype "passive"))
      (node (ref "R84") (pin "2") (pinfunction "2_2") (pintype "passive"))
      (node (ref "R85") (pin "2") (pinfunction "2_2") (pintype "passive"))
      (node (ref "R92") (pin "2") (pinfunction "2_2") (pintype "passive"))
      (node (ref "R93") (pin "2") (pinfunction "2_2") (pintype "passive"))
      (node (ref "R94") (pin "2") (pinfunction "2_2") (pintype "passive"))
      (node (ref "U16") (pin "1") (pinfunction "S2_1") (pintype "passive"))
      (node (ref "U16") (pin "3") (pinfunction "S1_3") (pintype "passive"))
      (node (ref "U17") (pin "1") (pinfunction "S2_1") (pintype "passive"))
      (node (ref "U17") (pin "3") (pinfunction "S1_3") (pintype "passive"))
      (node (ref "U18") (pin "1") (pinfunction "S2_1") (pintype "passive"))
      (node (ref "U18") (pin "3") (pinfunction "S1_3") (pintype "passive"))
      (node (ref "U31") (pin "1") (pinfunction "S2_1") (pintype "passive"))
      (node (ref "U31") (pin "3") (pinfunction "S1_3") (pintype "passive"))
      (node (ref "U32") (pin "1") (pinfunction "S2_1") (pintype "passive"))
      (node (ref "U32") (pin "3") (pinfunction "S1_3") (pintype "passive"))
      (node (ref "U33") (pin "1") (pinfunction "S2_1") (pintype "passive"))
      (node (ref "U33") (pin "3") (pinfunction "S1_3") (pintype "passive"))
      (node (ref "U46") (pin "1") (pinfunction "S2_1") (pintype "passive"))
      (node (ref "U46") (pin "3") (pinfunction "S1_3") (pintype "passive"))
      (node (ref "U47") (pin "1") (pinfunction "S2_1") (pintype "passive"))
      (node (ref "U47") (pin "3") (pinfunction "S1_3") (pintype "passive"))
      (node (ref "U48") (pin "1") (pinfunction "S2_1") (pintype "passive"))
      (node (ref "U48") (pin "3") (pinfunction "S1_3") (pintype "passive"))
      (node (ref "U61") (pin "1") (pinfunction "S2_1") (pintype "passive"))
      (node (ref "U61") (pin "3") (pinfunction "S1_3") (pintype "passive"))
      (node (ref "U62") (pin "1") (pinfunction "S2_1") (pintype "passive"))
      (node (ref "U62") (pin "3") (pinfunction "S1_3") (pintype "passive"))
      (node (ref "U63") (pin "1") (pinfunction "S2_1") (pintype "passive"))
      (node (ref "U63") (pin "3") (pinfunction "S1_3") (pintype "passive"))
      (node (ref "U74") (pin "1") (pinfunction "S2_1") (pintype "passive"))
      (node (ref "U74") (pin "3") (pinfunction "S1_3") (pintype "passive"))
      (node (ref "U75") (pin "1") (pinfunction "S2_1") (pintype "passive"))
      (node (ref "U75") (pin "3") (pinfunction "S1_3") (pintype "passive"))
    )
  )
)
